# AK4493-Combi9.net
KiCad netlist of a schematic drawn in EAGLE
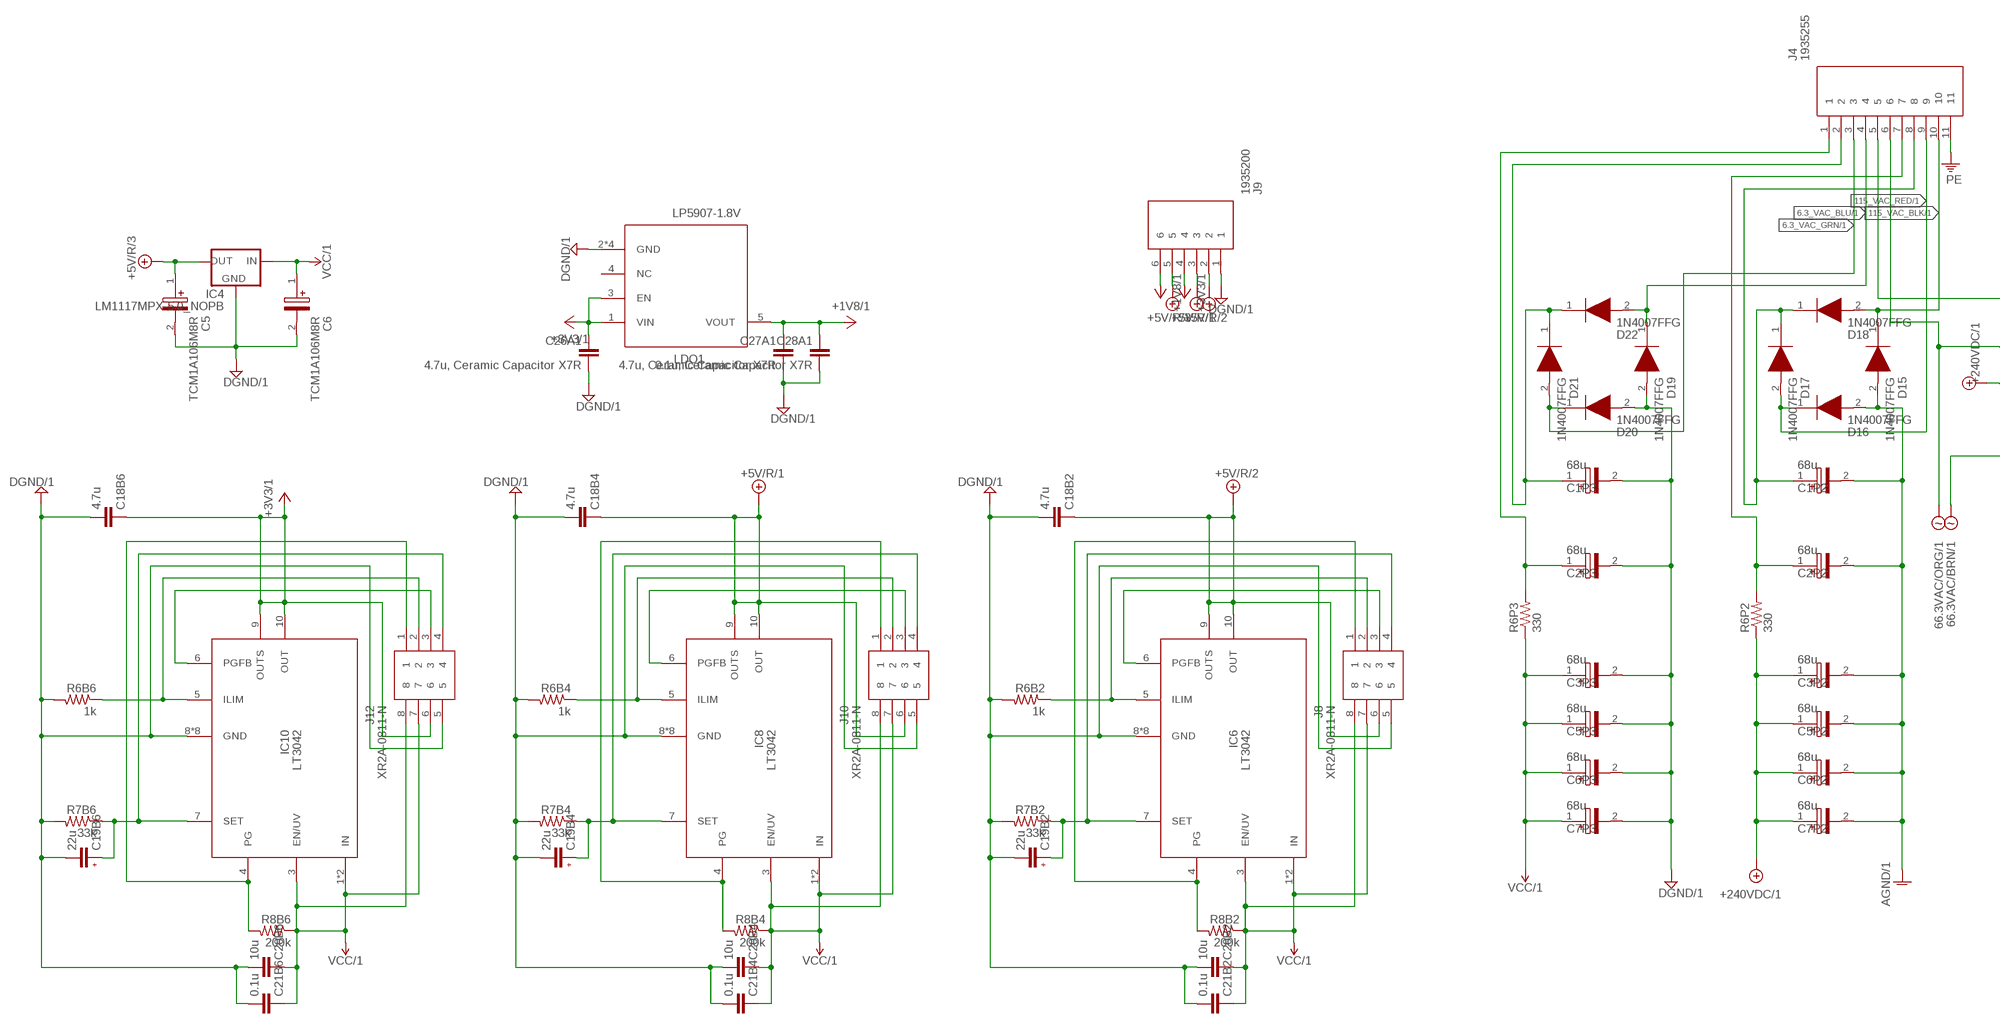
[diagram p0: schematic, sheet 1, part 1 of 3]
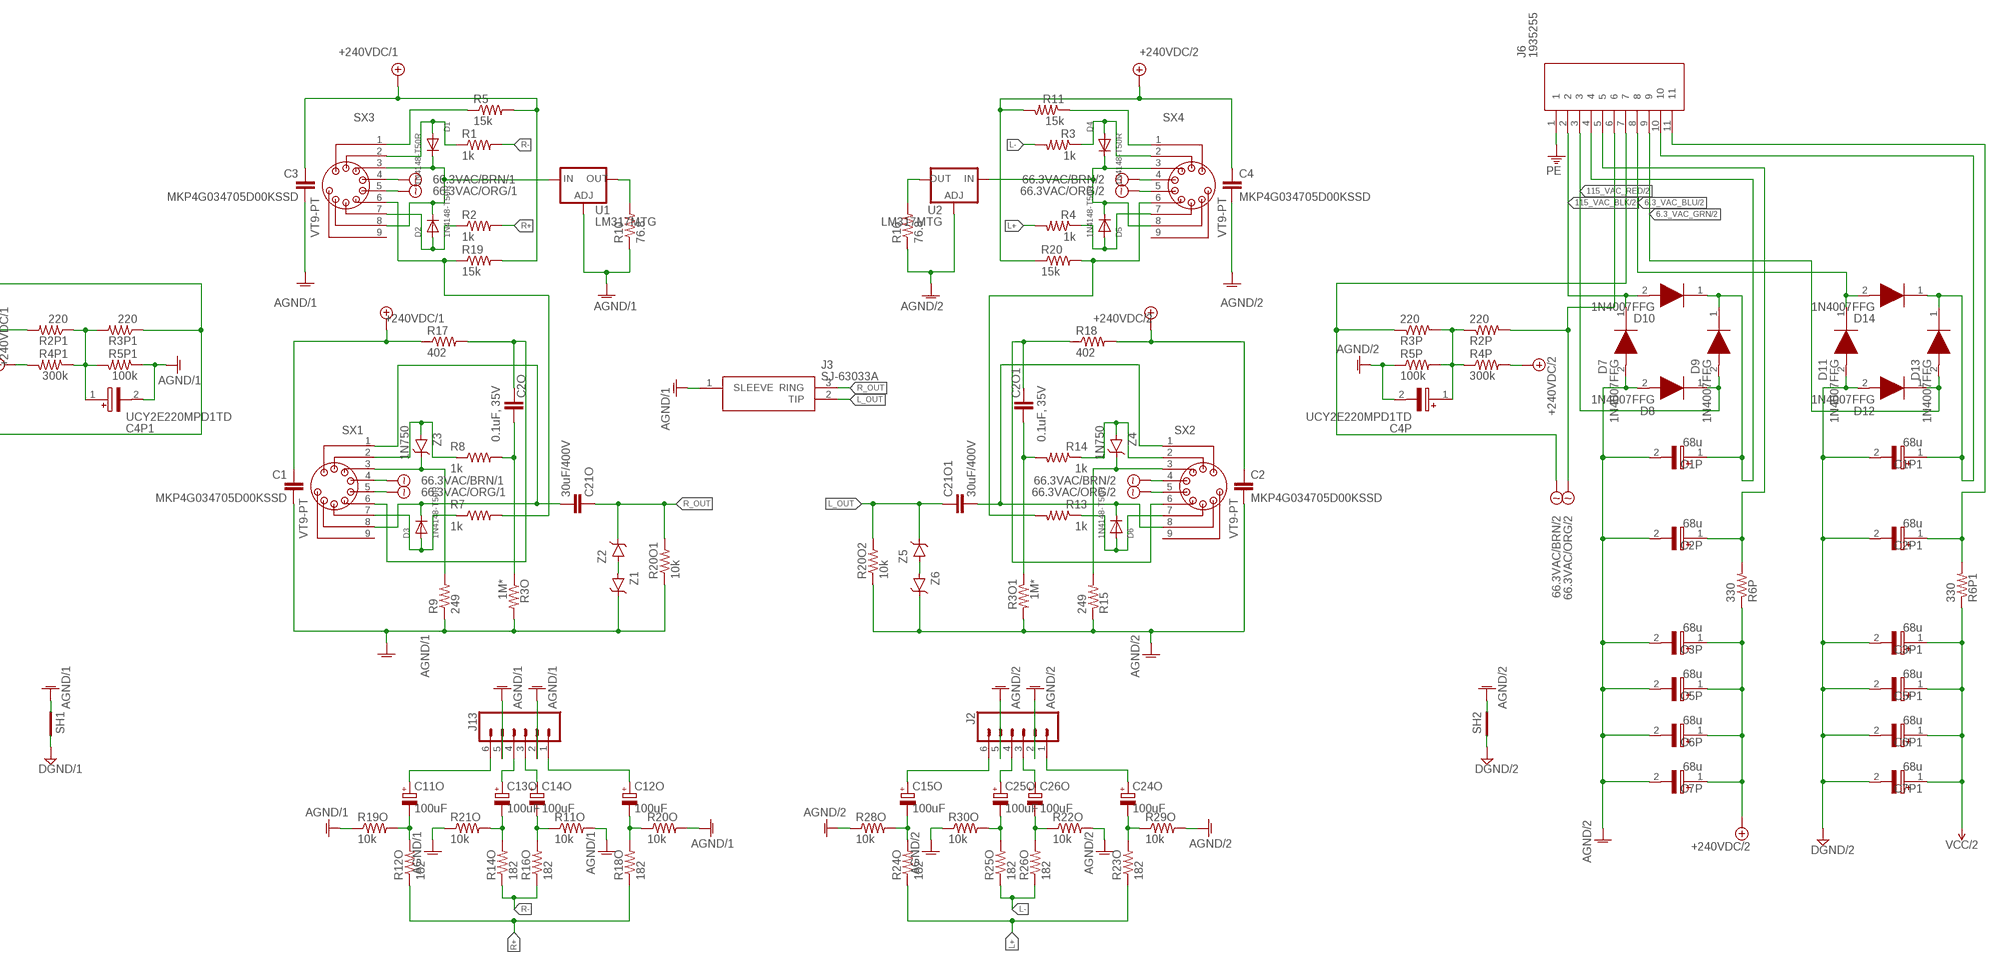
[diagram p1: schematic, sheet 1, part 2 of 3]
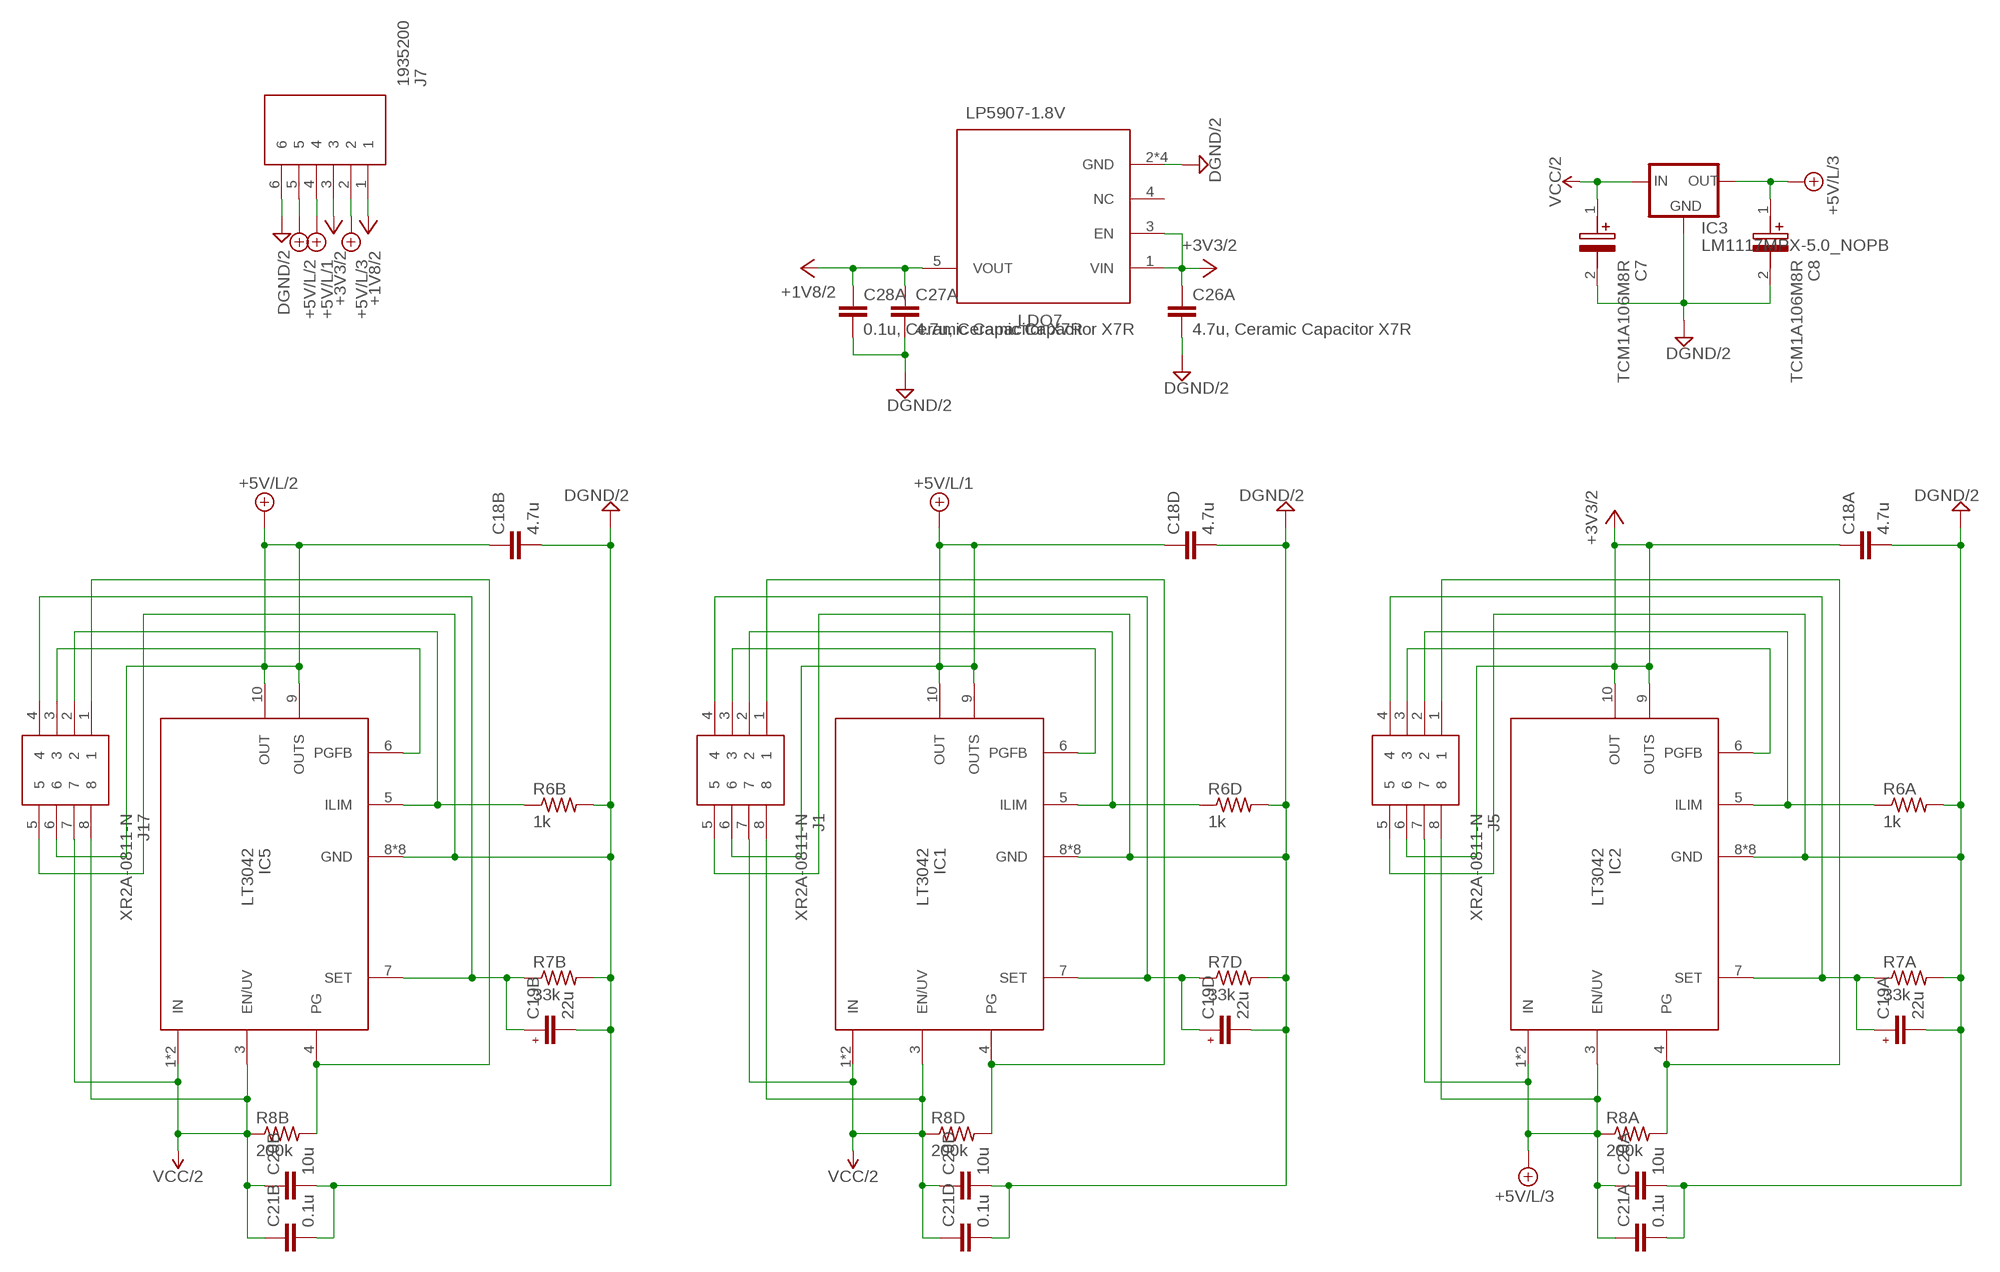
[diagram p2: schematic, sheet 1, part 3 of 3]

(export (version "E")
  (design (tool "Eeschema 10.0.6"))
  (components
    (comp (ref "C1")
      (value "MKP4G034705D00KSSD")
      (footprint "eagle-import:MKP4G034705D00KSSD")
      (fields (field (name "MOUSER_PART_NUMBER") "505-MKP4G034705DKSSD"))
      (libsource (lib "eagle-import") (part "MKP4G034705D00KSSD"))
    )
    (comp (ref "C1P")
      (value "68u")
      (footprint "eagle-import:CAPPRD750W80D1475H4700")
      (fields (field (name "MANUFACTURER_PART_NUMBER") "500HXW68MEFR14.5X45"))
      (libsource (lib "eagle-import") (part "500HXW68MEFR14.5X45"))
    )
    (comp (ref "C1P1")
      (value "68u")
      (footprint "eagle-import:CAPPRD750W80D1475H4700")
      (fields (field (name "MANUFACTURER_PART_NUMBER") "500HXW68MEFR14.5X45"))
      (libsource (lib "eagle-import") (part "500HXW68MEFR14.5X45"))
    )
    (comp (ref "C1P2")
      (value "68u")
      (footprint "eagle-import:CAPPRD750W80D1475H4700")
      (fields (field (name "MANUFACTURER_PART_NUMBER") "500HXW68MEFR14.5X45"))
      (libsource (lib "eagle-import") (part "500HXW68MEFR14.5X45"))
    )
    (comp (ref "C1P3")
      (value "68u")
      (footprint "eagle-import:CAPPRD750W80D1475H4700")
      (fields (field (name "MANUFACTURER_PART_NUMBER") "500HXW68MEFR14.5X45"))
      (libsource (lib "eagle-import") (part "500HXW68MEFR14.5X45"))
    )
    (comp (ref "C2")
      (value "MKP4G034705D00KSSD")
      (footprint "eagle-import:MKP4G034705D00KSSD")
      (fields (field (name "MOUSER_PART_NUMBER") "505-MKP4G034705DKSSD"))
      (libsource (lib "eagle-import") (part "MKP4G034705D00KSSD"))
    )
    (comp (ref "C2O")
      (value "0.1uF, 35V")
      (footprint "eagle-import:MKS4B031002A00JC00")
      (fields
        (field (name "MANUFACTURER_PART_NUMBER") "MKS4B031002A00JC00")
        (field (name "MOUSER_PART_NUMBER") "505-MKS4B0312AJC")
      )
      (libsource (lib "eagle-import") (part "MKS4B031002A00JC00"))
    )
    (comp (ref "C2O1")
      (value "0.1uF, 35V")
      (footprint "eagle-import:MKS4B031002A00JC00")
      (fields
        (field (name "MANUFACTURER_PART_NUMBER") "MKS4B031002A00JC00")
        (field (name "MOUSER_PART_NUMBER") "505-MKS4B0312AJC")
      )
      (libsource (lib "eagle-import") (part "MKS4B031002A00JC00"))
    )
    (comp (ref "C2P")
      (value "68u")
      (footprint "eagle-import:CAPPRD750W80D1475H4700")
      (fields (field (name "MANUFACTURER_PART_NUMBER") "500HXW68MEFR14.5X45"))
      (libsource (lib "eagle-import") (part "500HXW68MEFR14.5X45"))
    )
    (comp (ref "C2P1")
      (value "68u")
      (footprint "eagle-import:CAPPRD750W80D1475H4700")
      (fields (field (name "MANUFACTURER_PART_NUMBER") "500HXW68MEFR14.5X45"))
      (libsource (lib "eagle-import") (part "500HXW68MEFR14.5X45"))
    )
    (comp (ref "C2P2")
      (value "68u")
      (footprint "eagle-import:CAPPRD750W80D1475H4700")
      (fields (field (name "MANUFACTURER_PART_NUMBER") "500HXW68MEFR14.5X45"))
      (libsource (lib "eagle-import") (part "500HXW68MEFR14.5X45"))
    )
    (comp (ref "C2P3")
      (value "68u")
      (footprint "eagle-import:CAPPRD750W80D1475H4700")
      (fields (field (name "MANUFACTURER_PART_NUMBER") "500HXW68MEFR14.5X45"))
      (libsource (lib "eagle-import") (part "500HXW68MEFR14.5X45"))
    )
    (comp (ref "C3")
      (value "MKP4G034705D00KSSD")
      (footprint "eagle-import:MKP4G034705D00KSSD")
      (fields (field (name "MOUSER_PART_NUMBER") "505-MKP4G034705DKSSD"))
      (libsource (lib "eagle-import") (part "MKP4G034705D00KSSD"))
    )
    (comp (ref "C3P")
      (value "68u")
      (footprint "eagle-import:CAPPRD750W80D1475H4700")
      (fields (field (name "MANUFACTURER_PART_NUMBER") "500HXW68MEFR14.5X45"))
      (libsource (lib "eagle-import") (part "500HXW68MEFR14.5X45"))
    )
    (comp (ref "C3P1")
      (value "68u")
      (footprint "eagle-import:CAPPRD750W80D1475H4700")
      (fields (field (name "MANUFACTURER_PART_NUMBER") "500HXW68MEFR14.5X45"))
      (libsource (lib "eagle-import") (part "500HXW68MEFR14.5X45"))
    )
    (comp (ref "C3P2")
      (value "68u")
      (footprint "eagle-import:CAPPRD750W80D1475H4700")
      (fields (field (name "MANUFACTURER_PART_NUMBER") "500HXW68MEFR14.5X45"))
      (libsource (lib "eagle-import") (part "500HXW68MEFR14.5X45"))
    )
    (comp (ref "C3P3")
      (value "68u")
      (footprint "eagle-import:CAPPRD750W80D1475H4700")
      (fields (field (name "MANUFACTURER_PART_NUMBER") "500HXW68MEFR14.5X45"))
      (libsource (lib "eagle-import") (part "500HXW68MEFR14.5X45"))
    )
    (comp (ref "C4")
      (value "MKP4G034705D00KSSD")
      (footprint "eagle-import:MKP4G034705D00KSSD")
      (fields (field (name "MOUSER_PART_NUMBER") "505-MKP4G034705DKSSD"))
      (libsource (lib "eagle-import") (part "MKP4G034705D00KSSD"))
    )
    (comp (ref "C4P")
      (value "UCY2E220MPD1TD")
      (footprint "eagle-import:CAPPRD500W60D1025H1750")
      (fields (field (name "MOUSER_PART_NUMBER") "647-UCY2E220MPD1TD"))
      (libsource (lib "eagle-import") (part "UCY2E220MPD1TD"))
    )
    (comp (ref "C4P1")
      (value "UCY2E220MPD1TD")
      (footprint "eagle-import:CAPPRD500W60D1025H1750")
      (fields (field (name "MOUSER_PART_NUMBER") "647-UCY2E220MPD1TD"))
      (libsource (lib "eagle-import") (part "UCY2E220MPD1TD"))
    )
    (comp (ref "C5")
      (value "TCM1A106M8R")
      (footprint "eagle-import:CAPPM168X90N")
      (fields (field (name "MOUSER_PART_NUMBER") "755-TCM1A106M8R"))
      (libsource (lib "eagle-import") (part "TCM1A106M8R"))
    )
    (comp (ref "C5P")
      (value "68u")
      (footprint "eagle-import:CAPPRD750W80D1475H4700")
      (fields (field (name "MANUFACTURER_PART_NUMBER") "500HXW68MEFR14.5X45"))
      (libsource (lib "eagle-import") (part "500HXW68MEFR14.5X45"))
    )
    (comp (ref "C5P1")
      (value "68u")
      (footprint "eagle-import:CAPPRD750W80D1475H4700")
      (fields (field (name "MANUFACTURER_PART_NUMBER") "500HXW68MEFR14.5X45"))
      (libsource (lib "eagle-import") (part "500HXW68MEFR14.5X45"))
    )
    (comp (ref "C5P2")
      (value "68u")
      (footprint "eagle-import:CAPPRD750W80D1475H4700")
      (fields (field (name "MANUFACTURER_PART_NUMBER") "500HXW68MEFR14.5X45"))
      (libsource (lib "eagle-import") (part "500HXW68MEFR14.5X45"))
    )
    (comp (ref "C5P3")
      (value "68u")
      (footprint "eagle-import:CAPPRD750W80D1475H4700")
      (fields (field (name "MANUFACTURER_PART_NUMBER") "500HXW68MEFR14.5X45"))
      (libsource (lib "eagle-import") (part "500HXW68MEFR14.5X45"))
    )
    (comp (ref "C6")
      (value "TCM1A106M8R")
      (footprint "eagle-import:CAPPM168X90N")
      (fields (field (name "MOUSER_PART_NUMBER") "755-TCM1A106M8R"))
      (libsource (lib "eagle-import") (part "TCM1A106M8R"))
    )
    (comp (ref "C6P")
      (value "68u")
      (footprint "eagle-import:CAPPRD750W80D1475H4700")
      (fields (field (name "MANUFACTURER_PART_NUMBER") "500HXW68MEFR14.5X45"))
      (libsource (lib "eagle-import") (part "500HXW68MEFR14.5X45"))
    )
    (comp (ref "C6P1")
      (value "68u")
      (footprint "eagle-import:CAPPRD750W80D1475H4700")
      (fields (field (name "MANUFACTURER_PART_NUMBER") "500HXW68MEFR14.5X45"))
      (libsource (lib "eagle-import") (part "500HXW68MEFR14.5X45"))
    )
    (comp (ref "C6P2")
      (value "68u")
      (footprint "eagle-import:CAPPRD750W80D1475H4700")
      (fields (field (name "MANUFACTURER_PART_NUMBER") "500HXW68MEFR14.5X45"))
      (libsource (lib "eagle-import") (part "500HXW68MEFR14.5X45"))
    )
    (comp (ref "C6P3")
      (value "68u")
      (footprint "eagle-import:CAPPRD750W80D1475H4700")
      (fields (field (name "MANUFACTURER_PART_NUMBER") "500HXW68MEFR14.5X45"))
      (libsource (lib "eagle-import") (part "500HXW68MEFR14.5X45"))
    )
    (comp (ref "C7")
      (value "TCM1A106M8R")
      (footprint "eagle-import:CAPPM168X90N")
      (fields (field (name "MOUSER_PART_NUMBER") "755-TCM1A106M8R"))
      (libsource (lib "eagle-import") (part "TCM1A106M8R"))
    )
    (comp (ref "C7P")
      (value "68u")
      (footprint "eagle-import:CAPPRD750W80D1475H4700")
      (fields (field (name "MANUFACTURER_PART_NUMBER") "500HXW68MEFR14.5X45"))
      (libsource (lib "eagle-import") (part "500HXW68MEFR14.5X45"))
    )
    (comp (ref "C7P1")
      (value "68u")
      (footprint "eagle-import:CAPPRD750W80D1475H4700")
      (fields (field (name "MANUFACTURER_PART_NUMBER") "500HXW68MEFR14.5X45"))
      (libsource (lib "eagle-import") (part "500HXW68MEFR14.5X45"))
    )
    (comp (ref "C7P2")
      (value "68u")
      (footprint "eagle-import:CAPPRD750W80D1475H4700")
      (fields (field (name "MANUFACTURER_PART_NUMBER") "500HXW68MEFR14.5X45"))
      (libsource (lib "eagle-import") (part "500HXW68MEFR14.5X45"))
    )
    (comp (ref "C7P3")
      (value "68u")
      (footprint "eagle-import:CAPPRD750W80D1475H4700")
      (fields (field (name "MANUFACTURER_PART_NUMBER") "500HXW68MEFR14.5X45"))
      (libsource (lib "eagle-import") (part "500HXW68MEFR14.5X45"))
    )
    (comp (ref "C8")
      (value "TCM1A106M8R")
      (footprint "eagle-import:CAPPM168X90N")
      (fields (field (name "MOUSER_PART_NUMBER") "755-TCM1A106M8R"))
      (libsource (lib "eagle-import") (part "TCM1A106M8R"))
    )
    (comp (ref "C11O")
      (value "100uF")
      (footprint "eagle-import:CAPPRD350W60D825H1300")
      (fields
        (field (name "ARROW_PART_NUMBER") "UFW1H101MPD1TD")
        (field (name "MOUSER_PART_NUMBER") "647-UFW1H101MPD1TD")
      )
      (libsource (lib "eagle-import") (part "UFW1H101MPD1TD"))
    )
    (comp (ref "C12O")
      (value "100uF")
      (footprint "eagle-import:CAPPRD350W60D825H1300")
      (fields
        (field (name "ARROW_PART_NUMBER") "UFW1H101MPD1TD")
        (field (name "MOUSER_PART_NUMBER") "647-UFW1H101MPD1TD")
      )
      (libsource (lib "eagle-import") (part "UFW1H101MPD1TD"))
    )
    (comp (ref "C13O")
      (value "100uF")
      (footprint "eagle-import:CAPPRD350W60D825H1300")
      (fields
        (field (name "ARROW_PART_NUMBER") "UFW1H101MPD1TD")
        (field (name "MOUSER_PART_NUMBER") "647-UFW1H101MPD1TD")
      )
      (libsource (lib "eagle-import") (part "UFW1H101MPD1TD"))
    )
    (comp (ref "C14O")
      (value "100uF")
      (footprint "eagle-import:CAPPRD350W60D825H1300")
      (fields
        (field (name "ARROW_PART_NUMBER") "UFW1H101MPD1TD")
        (field (name "MOUSER_PART_NUMBER") "647-UFW1H101MPD1TD")
      )
      (libsource (lib "eagle-import") (part "UFW1H101MPD1TD"))
    )
    (comp (ref "C15O")
      (value "100uF")
      (footprint "eagle-import:CAPPRD350W60D825H1300")
      (fields
        (field (name "ARROW_PART_NUMBER") "UFW1H101MPD1TD")
        (field (name "MOUSER_PART_NUMBER") "647-UFW1H101MPD1TD")
      )
      (libsource (lib "eagle-import") (part "UFW1H101MPD1TD"))
    )
    (comp (ref "C18A")
      (value "4.7u")
      (footprint "eagle-import:CAPC2013X140N")
      (fields
        (field (name "MANUFACTURER_PART_NUMBER") "EMK212ABJ475KG-T")
        (field (name "MOUSER_PART_NUMBER") "963-EMK212ABJ475KG-T")
      )
      (libsource (lib "eagle-import") (part "EMK212ABJ475KG-T"))
    )
    (comp (ref "C18B")
      (value "4.7u")
      (footprint "eagle-import:CAPC2013X140N")
      (fields
        (field (name "MANUFACTURER_PART_NUMBER") "EMK212ABJ475KG-T")
        (field (name "MOUSER_PART_NUMBER") "963-EMK212ABJ475KG-T")
      )
      (libsource (lib "eagle-import") (part "EMK212ABJ475KG-T"))
    )
    (comp (ref "C18B2")
      (value "4.7u")
      (footprint "eagle-import:CAPC2013X140N")
      (fields
        (field (name "MANUFACTURER_PART_NUMBER") "EMK212ABJ475KG-T")
        (field (name "MOUSER_PART_NUMBER") "963-EMK212ABJ475KG-T")
      )
      (libsource (lib "eagle-import") (part "EMK212ABJ475KG-T"))
    )
    (comp (ref "C18B4")
      (value "4.7u")
      (footprint "eagle-import:CAPC2013X140N")
      (fields
        (field (name "MANUFACTURER_PART_NUMBER") "EMK212ABJ475KG-T")
        (field (name "MOUSER_PART_NUMBER") "963-EMK212ABJ475KG-T")
      )
      (libsource (lib "eagle-import") (part "EMK212ABJ475KG-T"))
    )
    (comp (ref "C18B6")
      (value "4.7u")
      (footprint "eagle-import:CAPC2013X140N")
      (fields
        (field (name "MANUFACTURER_PART_NUMBER") "EMK212ABJ475KG-T")
        (field (name "MOUSER_PART_NUMBER") "963-EMK212ABJ475KG-T")
      )
      (libsource (lib "eagle-import") (part "EMK212ABJ475KG-T"))
    )
    (comp (ref "C18D")
      (value "4.7u")
      (footprint "eagle-import:CAPC2013X140N")
      (fields
        (field (name "MANUFACTURER_PART_NUMBER") "EMK212ABJ475KG-T")
        (field (name "MOUSER_PART_NUMBER") "963-EMK212ABJ475KG-T")
      )
      (libsource (lib "eagle-import") (part "EMK212ABJ475KG-T"))
    )
    (comp (ref "C19A")
      (value "22u")
      (footprint "eagle-import:C1206")
      (fields
        (field (name "MANUFACTURER_PART_NUMBER") "EMK316BB7226ML-T")
        (field (name "MOUSER_PART_NUMBER") "963-EMK316BB7226ML-T")
      )
      (libsource (lib "eagle-import") (part "EMK316BB7226ML-T"))
    )
    (comp (ref "C19B")
      (value "22u")
      (footprint "eagle-import:C1206")
      (fields
        (field (name "MANUFACTURER_PART_NUMBER") "EMK316BB7226ML-T")
        (field (name "MOUSER_PART_NUMBER") "963-EMK316BB7226ML-T")
      )
      (libsource (lib "eagle-import") (part "EMK316BB7226ML-T"))
    )
    (comp (ref "C19B2")
      (value "22u")
      (footprint "eagle-import:C1206")
      (fields
        (field (name "MANUFACTURER_PART_NUMBER") "EMK316BB7226ML-T")
        (field (name "MOUSER_PART_NUMBER") "963-EMK316BB7226ML-T")
      )
      (libsource (lib "eagle-import") (part "EMK316BB7226ML-T"))
    )
    (comp (ref "C19B4")
      (value "22u")
      (footprint "eagle-import:C1206")
      (fields
        (field (name "MANUFACTURER_PART_NUMBER") "EMK316BB7226ML-T")
        (field (name "MOUSER_PART_NUMBER") "963-EMK316BB7226ML-T")
      )
      (libsource (lib "eagle-import") (part "EMK316BB7226ML-T"))
    )
    (comp (ref "C19B6")
      (value "22u")
      (footprint "eagle-import:C1206")
      (fields
        (field (name "MANUFACTURER_PART_NUMBER") "EMK316BB7226ML-T")
        (field (name "MOUSER_PART_NUMBER") "963-EMK316BB7226ML-T")
      )
      (libsource (lib "eagle-import") (part "EMK316BB7226ML-T"))
    )
    (comp (ref "C19D")
      (value "22u")
      (footprint "eagle-import:C1206")
      (fields
        (field (name "MANUFACTURER_PART_NUMBER") "EMK316BB7226ML-T")
        (field (name "MOUSER_PART_NUMBER") "963-EMK316BB7226ML-T")
      )
      (libsource (lib "eagle-import") (part "EMK316BB7226ML-T"))
    )
    (comp (ref "C20A")
      (value "10u")
      (footprint "eagle-import:CAPC2012X135N")
      (fields
        (field (name "MANUFACTURER_PART_NUMBER") "EMK212BB7106KG-T")
        (field (name "MOUSER_PART_NUMBER") "963-EMK212BB7106KG-T")
      )
      (libsource (lib "eagle-import") (part "EMK212BB7106KG-T"))
    )
    (comp (ref "C20B")
      (value "10u")
      (footprint "eagle-import:CAPC2012X135N")
      (fields
        (field (name "MANUFACTURER_PART_NUMBER") "EMK212BB7106KG-T")
        (field (name "MOUSER_PART_NUMBER") "963-EMK212BB7106KG-T")
      )
      (libsource (lib "eagle-import") (part "EMK212BB7106KG-T"))
    )
    (comp (ref "C20B2")
      (value "10u")
      (footprint "eagle-import:CAPC2012X135N")
      (fields
        (field (name "MANUFACTURER_PART_NUMBER") "EMK212BB7106KG-T")
        (field (name "MOUSER_PART_NUMBER") "963-EMK212BB7106KG-T")
      )
      (libsource (lib "eagle-import") (part "EMK212BB7106KG-T"))
    )
    (comp (ref "C20B4")
      (value "10u")
      (footprint "eagle-import:CAPC2012X135N")
      (fields
        (field (name "MANUFACTURER_PART_NUMBER") "EMK212BB7106KG-T")
        (field (name "MOUSER_PART_NUMBER") "963-EMK212BB7106KG-T")
      )
      (libsource (lib "eagle-import") (part "EMK212BB7106KG-T"))
    )
    (comp (ref "C20B6")
      (value "10u")
      (footprint "eagle-import:CAPC2012X135N")
      (fields
        (field (name "MANUFACTURER_PART_NUMBER") "EMK212BB7106KG-T")
        (field (name "MOUSER_PART_NUMBER") "963-EMK212BB7106KG-T")
      )
      (libsource (lib "eagle-import") (part "EMK212BB7106KG-T"))
    )
    (comp (ref "C20D")
      (value "10u")
      (footprint "eagle-import:CAPC2012X135N")
      (fields
        (field (name "MANUFACTURER_PART_NUMBER") "EMK212BB7106KG-T")
        (field (name "MOUSER_PART_NUMBER") "963-EMK212BB7106KG-T")
      )
      (libsource (lib "eagle-import") (part "EMK212BB7106KG-T"))
    )
    (comp (ref "C21A")
      (value "0.1u")
      (footprint "eagle-import:CAPC2012X135N")
      (fields
        (field (name "MANUFACTURER_PART_NUMBER") "EMF212B7104KGHT")
        (field (name "MOUSER_PART_NUMBER") "963-EMF212B7104KGHT")
      )
      (libsource (lib "eagle-import") (part "EMF212B7104KGHT"))
    )
    (comp (ref "C21B")
      (value "0.1u")
      (footprint "eagle-import:CAPC2012X135N")
      (fields
        (field (name "MANUFACTURER_PART_NUMBER") "EMF212B7104KGHT")
        (field (name "MOUSER_PART_NUMBER") "963-EMF212B7104KGHT")
      )
      (libsource (lib "eagle-import") (part "EMF212B7104KGHT"))
    )
    (comp (ref "C21B2")
      (value "0.1u")
      (footprint "eagle-import:CAPC2012X135N")
      (fields
        (field (name "MANUFACTURER_PART_NUMBER") "EMF212B7104KGHT")
        (field (name "MOUSER_PART_NUMBER") "963-EMF212B7104KGHT")
      )
      (libsource (lib "eagle-import") (part "EMF212B7104KGHT"))
    )
    (comp (ref "C21B4")
      (value "0.1u")
      (footprint "eagle-import:CAPC2012X135N")
      (fields
        (field (name "MANUFACTURER_PART_NUMBER") "EMF212B7104KGHT")
        (field (name "MOUSER_PART_NUMBER") "963-EMF212B7104KGHT")
      )
      (libsource (lib "eagle-import") (part "EMF212B7104KGHT"))
    )
    (comp (ref "C21B6")
      (value "0.1u")
      (footprint "eagle-import:CAPC2012X135N")
      (fields
        (field (name "MANUFACTURER_PART_NUMBER") "EMF212B7104KGHT")
        (field (name "MOUSER_PART_NUMBER") "963-EMF212B7104KGHT")
      )
      (libsource (lib "eagle-import") (part "EMF212B7104KGHT"))
    )
    (comp (ref "C21D")
      (value "0.1u")
      (footprint "eagle-import:CAPC2012X135N")
      (fields
        (field (name "MANUFACTURER_PART_NUMBER") "EMF212B7104KGHT")
        (field (name "MOUSER_PART_NUMBER") "963-EMF212B7104KGHT")
      )
      (libsource (lib "eagle-import") (part "EMF212B7104KGHT"))
    )
    (comp (ref "C21O")
      (value "30uF/400V")
      (footprint "eagle-import:DCP4G056007GD4KSSD")
      (fields
        (field (name "MANUFACTURER_PART_NUMBER") "DCP4G056007GD4KSSD")
        (field (name "MOUSER_PART_NUMBER") "505-DCP4G056007GD4KS")
      )
      (libsource (lib "eagle-import") (part "DCP4G056007GD4KSSD"))
    )
    (comp (ref "C21O1")
      (value "30uF/400V")
      (footprint "eagle-import:DCP4G056007GD4KSSD")
      (fields
        (field (name "MANUFACTURER_PART_NUMBER") "DCP4G056007GD4KSSD")
        (field (name "MOUSER_PART_NUMBER") "505-DCP4G056007GD4KS")
      )
      (libsource (lib "eagle-import") (part "DCP4G056007GD4KSSD"))
    )
    (comp (ref "C24O")
      (value "100uF")
      (footprint "eagle-import:CAPPRD350W60D825H1300")
      (fields
        (field (name "ARROW_PART_NUMBER") "UFW1H101MPD1TD")
        (field (name "MOUSER_PART_NUMBER") "647-UFW1H101MPD1TD")
      )
      (libsource (lib "eagle-import") (part "UFW1H101MPD1TD"))
    )
    (comp (ref "C25O")
      (value "100uF")
      (footprint "eagle-import:CAPPRD350W60D825H1300")
      (fields
        (field (name "ARROW_PART_NUMBER") "UFW1H101MPD1TD")
        (field (name "MOUSER_PART_NUMBER") "647-UFW1H101MPD1TD")
      )
      (libsource (lib "eagle-import") (part "UFW1H101MPD1TD"))
    )
    (comp (ref "C26A")
      (value "4.7u, Ceramic Capacitor X7R")
      (footprint "eagle-import:CAPC2013X140N")
      (fields
        (field (name "MANUFACTURER_PART_NUMBER") "EMK212ABJ475KG-T")
        (field (name "MOUSER_PART_NUMBER") "963-EMK212ABJ475KG-T")
      )
      (libsource (lib "eagle-import") (part "EMK212ABJ475KG-T"))
    )
    (comp (ref "C26A1")
      (value "4.7u, Ceramic Capacitor X7R")
      (footprint "eagle-import:CAPC2013X140N")
      (fields
        (field (name "MANUFACTURER_PART_NUMBER") "EMK212ABJ475KG-T")
        (field (name "MOUSER_PART_NUMBER") "963-EMK212ABJ475KG-T")
      )
      (libsource (lib "eagle-import") (part "EMK212ABJ475KG-T"))
    )
    (comp (ref "C26O")
      (value "100uF")
      (footprint "eagle-import:CAPPRD350W60D825H1300")
      (fields
        (field (name "ARROW_PART_NUMBER") "UFW1H101MPD1TD")
        (field (name "MOUSER_PART_NUMBER") "647-UFW1H101MPD1TD")
      )
      (libsource (lib "eagle-import") (part "UFW1H101MPD1TD"))
    )
    (comp (ref "C27A")
      (value "4.7u, Ceramic Capacitor X7R")
      (footprint "eagle-import:CAPC2013X140N")
      (fields
        (field (name "MANUFACTURER_PART_NUMBER") "EMK212ABJ475KG-T")
        (field (name "MOUSER_PART_NUMBER") "963-EMK212ABJ475KG-T")
      )
      (libsource (lib "eagle-import") (part "EMK212ABJ475KG-T"))
    )
    (comp (ref "C27A1")
      (value "4.7u, Ceramic Capacitor X7R")
      (footprint "eagle-import:CAPC2013X140N")
      (fields
        (field (name "MANUFACTURER_PART_NUMBER") "EMK212ABJ475KG-T")
        (field (name "MOUSER_PART_NUMBER") "963-EMK212ABJ475KG-T")
      )
      (libsource (lib "eagle-import") (part "EMK212ABJ475KG-T"))
    )
    (comp (ref "C28A")
      (value "0.1u, Ceramic Capacitor X7R")
      (footprint "eagle-import:CAPC2012X135N")
      (fields
        (field (name "MANUFACTURER_PART_NUMBER") "EMF212B7104KGHT")
        (field (name "MOUSER_PART_NUMBER") "963-EMF212B7104KGHT")
      )
      (libsource (lib "eagle-import") (part "EMF212B7104KGHT"))
    )
    (comp (ref "C28A1")
      (value "0.1u, Ceramic Capacitor X7R")
      (footprint "eagle-import:CAPC2012X135N")
      (fields
        (field (name "MANUFACTURER_PART_NUMBER") "EMF212B7104KGHT")
        (field (name "MOUSER_PART_NUMBER") "963-EMF212B7104KGHT")
      )
      (libsource (lib "eagle-import") (part "EMF212B7104KGHT"))
    )
    (comp (ref "D1")
      (value "1N4148-T50R")
      (footprint "eagle-import:DIOAD1068W53L380D172")
      (fields (field (name "MOUSER_PART_NUMBER") "512-1N4148T50R"))
      (libsource (lib "eagle-import") (part "1N4148-T50R"))
    )
    (comp (ref "D2")
      (value "1N4148-T50R")
      (footprint "eagle-import:DIOAD1068W53L380D172")
      (fields (field (name "MOUSER_PART_NUMBER") "512-1N4148T50R"))
      (libsource (lib "eagle-import") (part "1N4148-T50R"))
    )
    (comp (ref "D3")
      (value "1N4148-T50R")
      (footprint "eagle-import:DIOAD1068W53L380D172")
      (fields (field (name "MOUSER_PART_NUMBER") "512-1N4148T50R"))
      (libsource (lib "eagle-import") (part "1N4148-T50R"))
    )
    (comp (ref "D4")
      (value "1N4148-T50R")
      (footprint "eagle-import:DIOAD1068W53L380D172")
      (fields (field (name "MOUSER_PART_NUMBER") "512-1N4148T50R"))
      (libsource (lib "eagle-import") (part "1N4148-T50R"))
    )
    (comp (ref "D5")
      (value "1N4148-T50R")
      (footprint "eagle-import:DIOAD1068W53L380D172")
      (fields (field (name "MOUSER_PART_NUMBER") "512-1N4148T50R"))
      (libsource (lib "eagle-import") (part "1N4148-T50R"))
    )
    (comp (ref "D6")
      (value "1N4148-T50R")
      (footprint "eagle-import:DIOAD1068W53L380D172")
      (fields (field (name "MOUSER_PART_NUMBER") "512-1N4148T50R"))
      (libsource (lib "eagle-import") (part "1N4148-T50R"))
    )
    (comp (ref "D7")
      (value "1N4007FFG")
      (footprint "eagle-import:DIOAD1405W86L465D235")
      (fields (field (name "MOUSER_PART_NUMBER") "863-1N4007FFG"))
      (libsource (lib "eagle-import") (part "1N4007FFG"))
    )
    (comp (ref "D8")
      (value "1N4007FFG")
      (footprint "eagle-import:DIOAD1405W86L465D235")
      (fields (field (name "MOUSER_PART_NUMBER") "863-1N4007FFG"))
      (libsource (lib "eagle-import") (part "1N4007FFG"))
    )
    (comp (ref "D9")
      (value "1N4007FFG")
      (footprint "eagle-import:DIOAD1405W86L465D235")
      (fields (field (name "MOUSER_PART_NUMBER") "863-1N4007FFG"))
      (libsource (lib "eagle-import") (part "1N4007FFG"))
    )
    (comp (ref "D10")
      (value "1N4007FFG")
      (footprint "eagle-import:DIOAD1405W86L465D235")
      (fields (field (name "MOUSER_PART_NUMBER") "863-1N4007FFG"))
      (libsource (lib "eagle-import") (part "1N4007FFG"))
    )
    (comp (ref "D11")
      (value "1N4007FFG")
      (footprint "eagle-import:DIOAD1405W86L465D235")
      (fields (field (name "MOUSER_PART_NUMBER") "863-1N4007FFG"))
      (libsource (lib "eagle-import") (part "1N4007FFG"))
    )
    (comp (ref "D12")
      (value "1N4007FFG")
      (footprint "eagle-import:DIOAD1405W86L465D235")
      (fields (field (name "MOUSER_PART_NUMBER") "863-1N4007FFG"))
      (libsource (lib "eagle-import") (part "1N4007FFG"))
    )
    (comp (ref "D13")
      (value "1N4007FFG")
      (footprint "eagle-import:DIOAD1405W86L465D235")
      (fields (field (name "MOUSER_PART_NUMBER") "863-1N4007FFG"))
      (libsource (lib "eagle-import") (part "1N4007FFG"))
    )
    (comp (ref "D14")
      (value "1N4007FFG")
      (footprint "eagle-import:DIOAD1405W86L465D235")
      (fields (field (name "MOUSER_PART_NUMBER") "863-1N4007FFG"))
      (libsource (lib "eagle-import") (part "1N4007FFG"))
    )
    (comp (ref "D15")
      (value "1N4007FFG")
      (footprint "eagle-import:DIOAD1405W86L465D235")
      (fields (field (name "MOUSER_PART_NUMBER") "863-1N4007FFG"))
      (libsource (lib "eagle-import") (part "1N4007FFG"))
    )
    (comp (ref "D16")
      (value "1N4007FFG")
      (footprint "eagle-import:DIOAD1405W86L465D235")
      (fields (field (name "MOUSER_PART_NUMBER") "863-1N4007FFG"))
      (libsource (lib "eagle-import") (part "1N4007FFG"))
    )
    (comp (ref "D17")
      (value "1N4007FFG")
      (footprint "eagle-import:DIOAD1405W86L465D235")
      (fields (field (name "MOUSER_PART_NUMBER") "863-1N4007FFG"))
      (libsource (lib "eagle-import") (part "1N4007FFG"))
    )
    (comp (ref "D18")
      (value "1N4007FFG")
      (footprint "eagle-import:DIOAD1405W86L465D235")
      (fields (field (name "MOUSER_PART_NUMBER") "863-1N4007FFG"))
      (libsource (lib "eagle-import") (part "1N4007FFG"))
    )
    (comp (ref "D19")
      (value "1N4007FFG")
      (footprint "eagle-import:DIOAD1405W86L465D235")
      (fields (field (name "MOUSER_PART_NUMBER") "863-1N4007FFG"))
      (libsource (lib "eagle-import") (part "1N4007FFG"))
    )
    (comp (ref "D20")
      (value "1N4007FFG")
      (footprint "eagle-import:DIOAD1405W86L465D235")
      (fields (field (name "MOUSER_PART_NUMBER") "863-1N4007FFG"))
      (libsource (lib "eagle-import") (part "1N4007FFG"))
    )
    (comp (ref "D21")
      (value "1N4007FFG")
      (footprint "eagle-import:DIOAD1405W86L465D235")
      (fields (field (name "MOUSER_PART_NUMBER") "863-1N4007FFG"))
      (libsource (lib "eagle-import") (part "1N4007FFG"))
    )
    (comp (ref "D22")
      (value "1N4007FFG")
      (footprint "eagle-import:DIOAD1405W86L465D235")
      (fields (field (name "MOUSER_PART_NUMBER") "863-1N4007FFG"))
      (libsource (lib "eagle-import") (part "1N4007FFG"))
    )
    (comp (ref "IC1")
      (value "LT3042")
      (footprint "eagle-import:SOP50P490X110-11N")
      (fields
        (field (name "MANUFACTURER_PART_NUMBER") "LT3042EMSE#PBF")
        (field (name "MOUSER_PART_NUMBER") "584-LT3042EMSE#PBF")
      )
      (libsource (lib "eagle-import") (part "LT3042"))
    )
    (comp (ref "IC2")
      (value "LT3042")
      (footprint "eagle-import:SOP50P490X110-11N")
      (fields
        (field (name "MANUFACTURER_PART_NUMBER") "LT3042EMSE#PBF")
        (field (name "MOUSER_PART_NUMBER") "584-LT3042EMSE#PBF")
      )
      (libsource (lib "eagle-import") (part "LT3042"))
    )
    (comp (ref "IC3")
      (value "LM1117MPX-5.0_NOPB")
      (footprint "eagle-import:SOT230P700X180-4N")
      (fields
        (field (name "MANUFACTURER_PART_NUMBER") "LM1117MPX-5.0/NOPB")
        (field (name "MOUSER_PART_NUMBER") "926-LM1117MPX5.0NOPB")
      )
      (libsource (lib "eagle-import") (part "LM1117MPX-5.0_NOPB"))
    )
    (comp (ref "IC4")
      (value "LM1117MPX-5.0_NOPB")
      (footprint "eagle-import:SOT230P700X180-4N")
      (fields
        (field (name "MANUFACTURER_PART_NUMBER") "LM1117MPX-5.0/NOPB")
        (field (name "MOUSER_PART_NUMBER") "926-LM1117MPX5.0NOPB")
      )
      (libsource (lib "eagle-import") (part "LM1117MPX-5.0_NOPB"))
    )
    (comp (ref "IC5")
      (value "LT3042")
      (footprint "eagle-import:SOP50P490X110-11N")
      (fields
        (field (name "MANUFACTURER_PART_NUMBER") "LT3042EMSE#PBF")
        (field (name "MOUSER_PART_NUMBER") "584-LT3042EMSE#PBF")
      )
      (libsource (lib "eagle-import") (part "LT3042"))
    )
    (comp (ref "IC6")
      (value "LT3042")
      (footprint "eagle-import:SOP50P490X110-11N")
      (fields
        (field (name "MANUFACTURER_PART_NUMBER") "LT3042EMSE#PBF")
        (field (name "MOUSER_PART_NUMBER") "584-LT3042EMSE#PBF")
      )
      (libsource (lib "eagle-import") (part "LT3042"))
    )
    (comp (ref "IC8")
      (value "LT3042")
      (footprint "eagle-import:SOP50P490X110-11N")
      (fields
        (field (name "MANUFACTURER_PART_NUMBER") "LT3042EMSE#PBF")
        (field (name "MOUSER_PART_NUMBER") "584-LT3042EMSE#PBF")
      )
      (libsource (lib "eagle-import") (part "LT3042"))
    )
    (comp (ref "IC10")
      (value "LT3042")
      (footprint "eagle-import:SOP50P490X110-11N")
      (fields
        (field (name "MANUFACTURER_PART_NUMBER") "LT3042EMSE#PBF")
        (field (name "MOUSER_PART_NUMBER") "584-LT3042EMSE#PBF")
      )
      (libsource (lib "eagle-import") (part "LT3042"))
    )
    (comp (ref "J1")
      (value "XR2A-0811-N")
      (footprint "eagle-import:DIPS762W51P254L1016H390Q8N")
      (fields (field (name "MOUSER_PART_NUMBER") "653-XR2A-0811-N"))
      (libsource (lib "eagle-import") (part "XR2A-0811-N"))
    )
    (comp (ref "J2")
      (value "CONN_06SILK_FEMALE_PTH")
      (footprint "eagle-import:1X06")
      (libsource (lib "eagle-import") (part "CONN_06SILK_FEMALE_PTH"))
    )
    (comp (ref "J3")
      (value "SJ-63033A")
      (footprint "eagle-import:SJ63033A")
      (libsource (lib "eagle-import") (part "SJ-63033A"))
    )
    (comp (ref "J4")
      (value "1935255")
      (footprint "eagle-import:1935255")
      (fields (field (name "MOUSER_PART_NUMBER") "651-1935255"))
      (libsource (lib "eagle-import") (part "1935255"))
    )
    (comp (ref "J5")
      (value "XR2A-0811-N")
      (footprint "eagle-import:DIPS762W51P254L1016H390Q8N")
      (fields (field (name "MOUSER_PART_NUMBER") "653-XR2A-0811-N"))
      (libsource (lib "eagle-import") (part "XR2A-0811-N"))
    )
    (comp (ref "J6")
      (value "1935255")
      (footprint "eagle-import:1935255")
      (fields (field (name "MOUSER_PART_NUMBER") "651-1935255"))
      (libsource (lib "eagle-import") (part "Dual Mono Amp Library_47621477_1935255"))
    )
    (comp (ref "J7")
      (value "1935200")
      (footprint "eagle-import:1935200")
      (fields (field (name "MOUSER_PART_NUMBER") "651-1935200"))
      (libsource (lib "eagle-import") (part "Dual Mono Amp Library_47621477_1935200"))
    )
    (comp (ref "J8")
      (value "XR2A-0811-N")
      (footprint "eagle-import:DIPS762W51P254L1016H390Q8N")
      (fields (field (name "MOUSER_PART_NUMBER") "653-XR2A-0811-N"))
      (libsource (lib "eagle-import") (part "XR2A-0811-N"))
    )
    (comp (ref "J9")
      (value "1935200")
      (footprint "eagle-import:1935200")
      (fields (field (name "MOUSER_PART_NUMBER") "651-1935200"))
      (libsource (lib "eagle-import") (part "1935200"))
    )
    (comp (ref "J10")
      (value "XR2A-0811-N")
      (footprint "eagle-import:DIPS762W51P254L1016H390Q8N")
      (fields (field (name "MOUSER_PART_NUMBER") "653-XR2A-0811-N"))
      (libsource (lib "eagle-import") (part "XR2A-0811-N"))
    )
    (comp (ref "J12")
      (value "XR2A-0811-N")
      (footprint "eagle-import:DIPS762W51P254L1016H390Q8N")
      (fields (field (name "MOUSER_PART_NUMBER") "653-XR2A-0811-N"))
      (libsource (lib "eagle-import") (part "XR2A-0811-N"))
    )
    (comp (ref "J13")
      (value "CONN_06SILK_FEMALE_PTH")
      (footprint "eagle-import:1X06")
      (libsource (lib "eagle-import") (part "CONN_06SILK_FEMALE_PTH"))
    )
    (comp (ref "J17")
      (value "XR2A-0811-N")
      (footprint "eagle-import:DIPS762W51P254L1016H390Q8N")
      (fields (field (name "MOUSER_PART_NUMBER") "653-XR2A-0811-N"))
      (libsource (lib "eagle-import") (part "XR2A-0811-N"))
    )
    (comp (ref "LDO1")
      (value "LP5907-1.8V")
      (footprint "eagle-import:SOT95P280X145-5N")
      (fields
        (field (name "ARROW_PART_NUMBER") "LP5907MFX-1.8/NOPB")
        (field (name "MOUSER_PART_NUMBER") "595-LP5907MFX-1.8NPB")
      )
      (libsource (lib "eagle-import") (part "LP5907-1.8V"))
    )
    (comp (ref "LDO7")
      (value "LP5907-1.8V")
      (footprint "eagle-import:SOT95P280X145-5N")
      (fields
        (field (name "ARROW_PART_NUMBER") "LP5907MFX-1.8/NOPB")
        (field (name "MOUSER_PART_NUMBER") "595-LP5907MFX-1.8NPB")
      )
      (libsource (lib "eagle-import") (part "LP5907-1.8V"))
    )
    (comp (ref "R1")
      (value "1k")
      (footprint "eagle-import:0207_10")
      (fields
        (field (name "MANUFACTURER_PART_NUMBER") "LR1F1K0")
        (field (name "MOUSER_PART_NUMBER") "279-LR1F1K0")
      )
      (libsource (lib "eagle-import") (part "LR1F1K0"))
    )
    (comp (ref "R2")
      (value "1k")
      (footprint "eagle-import:0207_10")
      (fields
        (field (name "MANUFACTURER_PART_NUMBER") "LR1F1K0")
        (field (name "MOUSER_PART_NUMBER") "279-LR1F1K0")
      )
      (libsource (lib "eagle-import") (part "LR1F1K0"))
    )
    (comp (ref "R2P")
      (value "220")
      (footprint "eagle-import:0411_15")
      (libsource (lib "eagle-import") (part "R-US_0411/15"))
    )
    (comp (ref "R2P1")
      (value "220")
      (footprint "eagle-import:0411_15")
      (libsource (lib "eagle-import") (part "R-US_0411/15"))
    )
    (comp (ref "R3")
      (value "1k")
      (footprint "eagle-import:0207_10")
      (fields
        (field (name "MANUFACTURER_PART_NUMBER") "LR1F1K0")
        (field (name "MOUSER_PART_NUMBER") "279-LR1F1K0")
      )
      (libsource (lib "eagle-import") (part "LR1F1K0"))
    )
    (comp (ref "R3O")
      (value "1M*")
      (footprint "eagle-import:0207_10")
      (fields
        (field (name "MANUFACTURER_PART_NUMBER") "LR1F1M0")
        (field (name "MOUSER_PART_NUMBER") "279-LR1F1M0")
      )
      (libsource (lib "eagle-import") (part "LR1F1M0"))
    )
    (comp (ref "R3O1")
      (value "1M*")
      (footprint "eagle-import:0207_10")
      (fields
        (field (name "MANUFACTURER_PART_NUMBER") "LR1F1M0")
        (field (name "MOUSER_PART_NUMBER") "279-LR1F1M0")
      )
      (libsource (lib "eagle-import") (part "LR1F1M0"))
    )
    (comp (ref "R3P")
      (value "220")
      (footprint "eagle-import:0411_15")
      (libsource (lib "eagle-import") (part "R-US_0411/15"))
    )
    (comp (ref "R3P1")
      (value "220")
      (footprint "eagle-import:0411_15")
      (libsource (lib "eagle-import") (part "R-US_0411/15"))
    )
    (comp (ref "R4")
      (value "1k")
      (footprint "eagle-import:0207_10")
      (fields
        (field (name "MANUFACTURER_PART_NUMBER") "LR1F1K0")
        (field (name "MOUSER_PART_NUMBER") "279-LR1F1K0")
      )
      (libsource (lib "eagle-import") (part "LR1F1K0"))
    )
    (comp (ref "R4P")
      (value "300k")
      (footprint "eagle-import:0411_15")
      (libsource (lib "eagle-import") (part "R-US_0411/15"))
    )
    (comp (ref "R4P1")
      (value "300k")
      (footprint "eagle-import:0411_15")
      (libsource (lib "eagle-import") (part "R-US_0411/15"))
    )
    (comp (ref "R5")
      (value "15k")
      (footprint "eagle-import:0411_15")
      (fields
        (field (name "MANUFACTURER_PART_NUMBER") "CPF215K000FKE14")
        (field (name "MOUSER_PART_NUMBER") "71-CPF2-F-15K-E3")
      )
      (libsource (lib "eagle-import") (part "CPF215K000FKE14"))
    )
    (comp (ref "R5P")
      (value "100k")
      (footprint "eagle-import:0411_15")
      (libsource (lib "eagle-import") (part "R-US_0411/15"))
    )
    (comp (ref "R5P1")
      (value "100k")
      (footprint "eagle-import:0411_15")
      (libsource (lib "eagle-import") (part "R-US_0411/15"))
    )
    (comp (ref "R6A")
      (value "1k")
      (footprint "eagle-import:RESC2012X60N")
      (fields
        (field (name "MANUFACTURER_PART_NUMBER") "CHP0805-FX-1001ELF")
        (field (name "MOUSER_PART_NUMBER") "652-CHP0805FX1001ELF")
      )
      (libsource (lib "eagle-import") (part "CHP0805-FX-1001ELF"))
    )
    (comp (ref "R6B")
      (value "1k")
      (footprint "eagle-import:RESC2012X60N")
      (fields
        (field (name "MANUFACTURER_PART_NUMBER") "CHP0805-FX-1001ELF")
        (field (name "MOUSER_PART_NUMBER") "652-CHP0805FX1001ELF")
      )
      (libsource (lib "eagle-import") (part "CHP0805-FX-1001ELF"))
    )
    (comp (ref "R6B2")
      (value "1k")
      (footprint "eagle-import:RESC2012X60N")
      (fields
        (field (name "MANUFACTURER_PART_NUMBER") "CHP0805-FX-1001ELF")
        (field (name "MOUSER_PART_NUMBER") "652-CHP0805FX1001ELF")
      )
      (libsource (lib "eagle-import") (part "CHP0805-FX-1001ELF"))
    )
    (comp (ref "R6B4")
      (value "1k")
      (footprint "eagle-import:RESC2012X60N")
      (fields
        (field (name "MANUFACTURER_PART_NUMBER") "CHP0805-FX-1001ELF")
        (field (name "MOUSER_PART_NUMBER") "652-CHP0805FX1001ELF")
      )
      (libsource (lib "eagle-import") (part "CHP0805-FX-1001ELF"))
    )
    (comp (ref "R6B6")
      (value "1k")
      (footprint "eagle-import:RESC2012X60N")
      (fields
        (field (name "MANUFACTURER_PART_NUMBER") "CHP0805-FX-1001ELF")
        (field (name "MOUSER_PART_NUMBER") "652-CHP0805FX1001ELF")
      )
      (libsource (lib "eagle-import") (part "CHP0805-FX-1001ELF"))
    )
    (comp (ref "R6D")
      (value "1k")
      (footprint "eagle-import:RESC2012X60N")
      (fields
        (field (name "MANUFACTURER_PART_NUMBER") "CHP0805-FX-1001ELF")
        (field (name "MOUSER_PART_NUMBER") "652-CHP0805FX1001ELF")
      )
      (libsource (lib "eagle-import") (part "CHP0805-FX-1001ELF"))
    )
    (comp (ref "R6P")
      (value "330")
      (footprint "eagle-import:0411_15")
      (libsource (lib "eagle-import") (part "R-US_0411/15"))
    )
    (comp (ref "R6P1")
      (value "330")
      (footprint "eagle-import:0411_15")
      (libsource (lib "eagle-import") (part "R-US_0411/15"))
    )
    (comp (ref "R6P2")
      (value "330")
      (footprint "eagle-import:0411_15")
      (libsource (lib "eagle-import") (part "R-US_0411/15"))
    )
    (comp (ref "R6P3")
      (value "330")
      (footprint "eagle-import:0411_15")
      (libsource (lib "eagle-import") (part "R-US_0411/15"))
    )
    (comp (ref "R7")
      (value "1k")
      (footprint "eagle-import:0207_10")
      (fields
        (field (name "MANUFACTURER_PART_NUMBER") "LR1F1K0")
        (field (name "MOUSER_PART_NUMBER") "279-LR1F1K0")
      )
      (libsource (lib "eagle-import") (part "LR1F1K0"))
    )
    (comp (ref "R7A")
      (value "33k")
      (footprint "eagle-import:R0805")
      (fields
        (field (name "MANUFACTURER_PART_NUMBER") "CPF0805B51KE1")
        (field (name "MOUSER_PART_NUMBER") "279-CPF0805B51KE1")
      )
      (libsource (lib "eagle-import") (part "CPF0805B51KE1"))
    )
    (comp (ref "R7B")
      (value "33k")
      (footprint "eagle-import:R0805")
      (fields
        (field (name "MANUFACTURER_PART_NUMBER") "CPF0805B51KE1")
        (field (name "MOUSER_PART_NUMBER") "279-CPF0805B51KE1")
      )
      (libsource (lib "eagle-import") (part "CPF0805B51KE1"))
    )
    (comp (ref "R7B2")
      (value "33k")
      (footprint "eagle-import:R0805")
      (fields
        (field (name "MANUFACTURER_PART_NUMBER") "CPF0805B51KE1")
        (field (name "MOUSER_PART_NUMBER") "279-CPF0805B51KE1")
      )
      (libsource (lib "eagle-import") (part "CPF0805B51KE1"))
    )
    (comp (ref "R7B4")
      (value "33k")
      (footprint "eagle-import:R0805")
      (fields
        (field (name "MANUFACTURER_PART_NUMBER") "CPF0805B51KE1")
        (field (name "MOUSER_PART_NUMBER") "279-CPF0805B51KE1")
      )
      (libsource (lib "eagle-import") (part "CPF0805B51KE1"))
    )
    (comp (ref "R7B6")
      (value "33k")
      (footprint "eagle-import:R0805")
      (fields
        (field (name "MANUFACTURER_PART_NUMBER") "CPF0805B51KE1")
        (field (name "MOUSER_PART_NUMBER") "279-CPF0805B51KE1")
      )
      (libsource (lib "eagle-import") (part "CPF0805B51KE1"))
    )
    (comp (ref "R7D")
      (value "33k")
      (footprint "eagle-import:R0805")
      (fields
        (field (name "MANUFACTURER_PART_NUMBER") "CPF0805B51KE1")
        (field (name "MOUSER_PART_NUMBER") "279-CPF0805B51KE1")
      )
      (libsource (lib "eagle-import") (part "CPF0805B51KE1"))
    )
    (comp (ref "R8")
      (value "1k")
      (footprint "eagle-import:0207_10")
      (fields
        (field (name "MANUFACTURER_PART_NUMBER") "LR1F1K0")
        (field (name "MOUSER_PART_NUMBER") "279-LR1F1K0")
      )
      (libsource (lib "eagle-import") (part "LR1F1K0"))
    )
    (comp (ref "R8A")
      (value "200k")
      (footprint "eagle-import:R0805")
      (fields
        (field (name "MANUFACTURER_PART_NUMBER") "RR1220P-204-D")
        (field (name "MOUSER_PART_NUMBER") "754-RR1220P-204D")
      )
      (libsource (lib "eagle-import") (part "RR1220P-204-D"))
    )
    (comp (ref "R8B")
      (value "200k")
      (footprint "eagle-import:R0805")
      (fields
        (field (name "MANUFACTURER_PART_NUMBER") "RR1220P-204-D")
        (field (name "MOUSER_PART_NUMBER") "754-RR1220P-204D")
      )
      (libsource (lib "eagle-import") (part "RR1220P-204-D"))
    )
    (comp (ref "R8B2")
      (value "200k")
      (footprint "eagle-import:R0805")
      (fields
        (field (name "MANUFACTURER_PART_NUMBER") "RR1220P-204-D")
        (field (name "MOUSER_PART_NUMBER") "754-RR1220P-204D")
      )
      (libsource (lib "eagle-import") (part "RR1220P-204-D"))
    )
    (comp (ref "R8B4")
      (value "200k")
      (footprint "eagle-import:R0805")
      (fields
        (field (name "MANUFACTURER_PART_NUMBER") "RR1220P-204-D")
        (field (name "MOUSER_PART_NUMBER") "754-RR1220P-204D")
      )
      (libsource (lib "eagle-import") (part "RR1220P-204-D"))
    )
    (comp (ref "R8B6")
      (value "200k")
      (footprint "eagle-import:R0805")
      (fields
        (field (name "MANUFACTURER_PART_NUMBER") "RR1220P-204-D")
        (field (name "MOUSER_PART_NUMBER") "754-RR1220P-204D")
      )
      (libsource (lib "eagle-import") (part "RR1220P-204-D"))
    )
    (comp (ref "R8D")
      (value "200k")
      (footprint "eagle-import:R0805")
      (fields
        (field (name "MANUFACTURER_PART_NUMBER") "RR1220P-204-D")
        (field (name "MOUSER_PART_NUMBER") "754-RR1220P-204D")
      )
      (libsource (lib "eagle-import") (part "RR1220P-204-D"))
    )
    (comp (ref "R9")
      (value "249")
      (footprint "eagle-import:0207_10")
      (fields (field (name "MANUFACTURER_PART_NUMBER") "MBB02070C2490FRP00"))
      (libsource (lib "eagle-import") (part "MBB02070C2490FRP00"))
    )
    (comp (ref "R10")
      (value "76.8")
      (footprint "eagle-import:0207_10")
      (fields (field (name "MANUFACTURER_PART_NUMBER") "YR1B76R8CC"))
      (libsource (lib "eagle-import") (part "YR1B76R8CC"))
    )
    (comp (ref "R11")
      (value "15k")
      (footprint "eagle-import:0411_15")
      (fields
        (field (name "MANUFACTURER_PART_NUMBER") "CPF215K000FKE14")
        (field (name "MOUSER_PART_NUMBER") "71-CPF2-F-15K-E3")
      )
      (libsource (lib "eagle-import") (part "CPF215K000FKE14"))
    )
    (comp (ref "R11O")
      (value "10k")
      (footprint "eagle-import:0207_10")
      (fields
        (field (name "MANUFACTURER_PART_NUMBER") "LR1F10K")
        (field (name "MOUSER_PART_NUMBER") "279-LR1F10K")
      )
      (libsource (lib "eagle-import") (part "LR1F10K"))
    )
    (comp (ref "R12O")
      (value "182")
      (footprint "eagle-import:0207_10")
      (fields
        (field (name "MANUFACTURER") "Yageo")
        (field (name "MANUFACTURER_PART_NUMBER") "MF0207FTE52-182R")
        (field (name "MOUSER_PART_NUMBER") "603-MF0207FTE52-182R")
      )
      (libsource (lib "eagle-import") (part "MF0207FTE52-182R"))
    )
    (comp (ref "R13")
      (value "1k")
      (footprint "eagle-import:0207_10")
      (fields
        (field (name "MANUFACTURER_PART_NUMBER") "LR1F1K0")
        (field (name "MOUSER_PART_NUMBER") "279-LR1F1K0")
      )
      (libsource (lib "eagle-import") (part "LR1F1K0"))
    )
    (comp (ref "R14")
      (value "1k")
      (footprint "eagle-import:0207_10")
      (fields
        (field (name "MANUFACTURER_PART_NUMBER") "LR1F1K0")
        (field (name "MOUSER_PART_NUMBER") "279-LR1F1K0")
      )
      (libsource (lib "eagle-import") (part "LR1F1K0"))
    )
    (comp (ref "R14O")
      (value "182")
      (footprint "eagle-import:0207_10")
      (fields
        (field (name "MANUFACTURER") "Yageo")
        (field (name "MANUFACTURER_PART_NUMBER") "MF0207FTE52-182R")
        (field (name "MOUSER_PART_NUMBER") "603-MF0207FTE52-182R")
      )
      (libsource (lib "eagle-import") (part "MF0207FTE52-182R"))
    )
    (comp (ref "R15")
      (value "249")
      (footprint "eagle-import:0207_10")
      (fields (field (name "MANUFACTURER_PART_NUMBER") "MBB02070C2490FRP00"))
      (libsource (lib "eagle-import") (part "MBB02070C2490FRP00"))
    )
    (comp (ref "R16")
      (value "76.8")
      (footprint "eagle-import:0207_10")
      (fields (field (name "MANUFACTURER_PART_NUMBER") "YR1B76R8CC"))
      (libsource (lib "eagle-import") (part "YR1B76R8CC"))
    )
    (comp (ref "R16O")
      (value "182")
      (footprint "eagle-import:0207_10")
      (fields
        (field (name "MANUFACTURER") "Yageo")
        (field (name "MANUFACTURER_PART_NUMBER") "MF0207FTE52-182R")
        (field (name "MOUSER_PART_NUMBER") "603-MF0207FTE52-182R")
      )
      (libsource (lib "eagle-import") (part "MF0207FTE52-182R"))
    )
    (comp (ref "R17")
      (value "402")
      (footprint "eagle-import:0617_22")
      (fields (field (name "MANUFACTURER_PART_NUMBER") "RWR80S4020FRB12"))
      (libsource (lib "eagle-import") (part "RWR80S4020FRB12"))
    )
    (comp (ref "R18")
      (value "402")
      (footprint "eagle-import:0617_22")
      (fields (field (name "MANUFACTURER_PART_NUMBER") "RWR80S4020FRB12"))
      (libsource (lib "eagle-import") (part "RWR80S4020FRB12"))
    )
    (comp (ref "R18O")
      (value "182")
      (footprint "eagle-import:0207_10")
      (fields
        (field (name "MANUFACTURER") "Yageo")
        (field (name "MANUFACTURER_PART_NUMBER") "MF0207FTE52-182R")
        (field (name "MOUSER_PART_NUMBER") "603-MF0207FTE52-182R")
      )
      (libsource (lib "eagle-import") (part "MF0207FTE52-182R"))
    )
    (comp (ref "R19")
      (value "15k")
      (footprint "eagle-import:0411_15")
      (fields
        (field (name "MANUFACTURER_PART_NUMBER") "CPF215K000FKE14")
        (field (name "MOUSER_PART_NUMBER") "71-CPF2-F-15K-E3")
      )
      (libsource (lib "eagle-import") (part "CPF215K000FKE14"))
    )
    (comp (ref "R19O")
      (value "10k")
      (footprint "eagle-import:0207_10")
      (fields
        (field (name "MANUFACTURER_PART_NUMBER") "LR1F10K")
        (field (name "MOUSER_PART_NUMBER") "279-LR1F10K")
      )
      (libsource (lib "eagle-import") (part "LR1F10K"))
    )
    (comp (ref "R20")
      (value "15k")
      (footprint "eagle-import:0411_15")
      (fields
        (field (name "MANUFACTURER_PART_NUMBER") "CPF215K000FKE14")
        (field (name "MOUSER_PART_NUMBER") "71-CPF2-F-15K-E3")
      )
      (libsource (lib "eagle-import") (part "CPF215K000FKE14"))
    )
    (comp (ref "R20O")
      (value "10k")
      (footprint "eagle-import:0207_10")
      (fields
        (field (name "MANUFACTURER_PART_NUMBER") "LR1F10K")
        (field (name "MOUSER_PART_NUMBER") "279-LR1F10K")
      )
      (libsource (lib "eagle-import") (part "LR1F10K"))
    )
    (comp (ref "R20O1")
      (value "10k")
      (footprint "eagle-import:0207_10")
      (fields
        (field (name "MANUFACTURER_PART_NUMBER") "LR1F10K")
        (field (name "MOUSER_PART_NUMBER") "279-LR1F10K")
      )
      (libsource (lib "eagle-import") (part "LR1F10K"))
    )
    (comp (ref "R20O2")
      (value "10k")
      (footprint "eagle-import:0207_10")
      (fields
        (field (name "MANUFACTURER_PART_NUMBER") "LR1F10K")
        (field (name "MOUSER_PART_NUMBER") "279-LR1F10K")
      )
      (libsource (lib "eagle-import") (part "LR1F10K"))
    )
    (comp (ref "R21O")
      (value "10k")
      (footprint "eagle-import:0207_10")
      (fields
        (field (name "MANUFACTURER_PART_NUMBER") "LR1F10K")
        (field (name "MOUSER_PART_NUMBER") "279-LR1F10K")
      )
      (libsource (lib "eagle-import") (part "LR1F10K"))
    )
    (comp (ref "R22O")
      (value "10k")
      (footprint "eagle-import:0207_10")
      (fields
        (field (name "MANUFACTURER_PART_NUMBER") "LR1F10K")
        (field (name "MOUSER_PART_NUMBER") "279-LR1F10K")
      )
      (libsource (lib "eagle-import") (part "LR1F10K"))
    )
    (comp (ref "R23O")
      (value "182")
      (footprint "eagle-import:0207_10")
      (fields
        (field (name "MANUFACTURER") "Yageo")
        (field (name "MANUFACTURER_PART_NUMBER") "MF0207FTE52-182R")
        (field (name "MOUSER_PART_NUMBER") "603-MF0207FTE52-182R")
      )
      (libsource (lib "eagle-import") (part "MF0207FTE52-182R"))
    )
    (comp (ref "R24O")
      (value "182")
      (footprint "eagle-import:0207_10")
      (fields
        (field (name "MANUFACTURER") "Yageo")
        (field (name "MANUFACTURER_PART_NUMBER") "MF0207FTE52-182R")
        (field (name "MOUSER_PART_NUMBER") "603-MF0207FTE52-182R")
      )
      (libsource (lib "eagle-import") (part "MF0207FTE52-182R"))
    )
    (comp (ref "R25O")
      (value "182")
      (footprint "eagle-import:0207_10")
      (fields
        (field (name "MANUFACTURER") "Yageo")
        (field (name "MANUFACTURER_PART_NUMBER") "MF0207FTE52-182R")
        (field (name "MOUSER_PART_NUMBER") "603-MF0207FTE52-182R")
      )
      (libsource (lib "eagle-import") (part "MF0207FTE52-182R"))
    )
    (comp (ref "R26O")
      (value "182")
      (footprint "eagle-import:0207_10")
      (fields
        (field (name "MANUFACTURER") "Yageo")
        (field (name "MANUFACTURER_PART_NUMBER") "MF0207FTE52-182R")
        (field (name "MOUSER_PART_NUMBER") "603-MF0207FTE52-182R")
      )
      (libsource (lib "eagle-import") (part "MF0207FTE52-182R"))
    )
    (comp (ref "R28O")
      (value "10k")
      (footprint "eagle-import:0207_10")
      (fields
        (field (name "MANUFACTURER_PART_NUMBER") "LR1F10K")
        (field (name "MOUSER_PART_NUMBER") "279-LR1F10K")
      )
      (libsource (lib "eagle-import") (part "LR1F10K"))
    )
    (comp (ref "R29O")
      (value "10k")
      (footprint "eagle-import:0207_10")
      (fields
        (field (name "MANUFACTURER_PART_NUMBER") "LR1F10K")
        (field (name "MOUSER_PART_NUMBER") "279-LR1F10K")
      )
      (libsource (lib "eagle-import") (part "LR1F10K"))
    )
    (comp (ref "R30O")
      (value "10k")
      (footprint "eagle-import:0207_10")
      (fields
        (field (name "MANUFACTURER_PART_NUMBER") "LR1F10K")
        (field (name "MOUSER_PART_NUMBER") "279-LR1F10K")
      )
      (libsource (lib "eagle-import") (part "LR1F10K"))
    )
    (comp (ref "SH1")
      (value "SHORTA5")
      (footprint "eagle-import:SHORT_ALL-50")
      (libsource (lib "eagle-import") (part "SHORTA5"))
    )
    (comp (ref "SH2")
      (value "SHORTA5")
      (footprint "eagle-import:SHORT_ALL-50")
      (libsource (lib "eagle-import") (part "SHORTA5"))
    )
    (comp (ref "SX1")
      (value "VT9-PT")
      (footprint "eagle-import:VT9-PT")
      (libsource (lib "eagle-import") (part "VT9-PT"))
    )
    (comp (ref "SX2")
      (value "VT9-PT")
      (footprint "eagle-import:VT9-PT")
      (libsource (lib "eagle-import") (part "VT9-PT"))
    )
    (comp (ref "SX3")
      (value "VT9-PT")
      (footprint "eagle-import:VT9-PT")
      (libsource (lib "eagle-import") (part "VT9-PT"))
    )
    (comp (ref "SX4")
      (value "VT9-PT")
      (footprint "eagle-import:VT9-PT")
      (libsource (lib "eagle-import") (part "VT9-PT"))
    )
    (comp (ref "U1")
      (value "LM317MTG")
      (footprint "eagle-import:TO254P482X997X2018-3P")
      (fields (field (name "MOUSER_PART_NUMBER") "863-LM317MTG"))
      (libsource (lib "eagle-import") (part "LM317MTG"))
    )
    (comp (ref "U2")
      (value "LM317MTG")
      (footprint "eagle-import:TO254P482X997X2018-3P")
      (fields (field (name "MOUSER_PART_NUMBER") "863-LM317MTG"))
      (libsource (lib "eagle-import") (part "LM317MTG"))
    )
    (comp (ref "Z1")
      (value "BZX79-C16,113")
      (footprint "eagle-import:DIOAD1165W56L425D185")
      (libsource (lib "eagle-import") (part "BZX79-C16,113"))
    )
    (comp (ref "Z2")
      (value "BZX79-C16,113")
      (footprint "eagle-import:DIOAD1165W56L425D185")
      (libsource (lib "eagle-import") (part "BZX79-C16,113"))
    )
    (comp (ref "Z3")
      (value "1N750")
      (footprint "eagle-import:DIOAD1256W56L444D203")
      (fields (field (name "MOUSER_PART_NUMBER") "494-1N750(DO-35)"))
      (libsource (lib "eagle-import") (part "1N750"))
    )
    (comp (ref "Z4")
      (value "1N750")
      (footprint "eagle-import:DIOAD1256W56L444D203")
      (fields (field (name "MOUSER_PART_NUMBER") "494-1N750(DO-35)"))
      (libsource (lib "eagle-import") (part "1N750"))
    )
    (comp (ref "Z5")
      (value "BZX79-C16,113")
      (footprint "eagle-import:DIOAD1165W56L425D185")
      (libsource (lib "eagle-import") (part "BZX79-C16,113"))
    )
    (comp (ref "Z6")
      (value "BZX79-C16,113")
      (footprint "eagle-import:DIOAD1165W56L425D185")
      (libsource (lib "eagle-import") (part "BZX79-C16,113"))
    )
  )
  (nets
    (net (code "1") (name "+1V8{slash}1") (class "Default")
      (node (ref "C27A1") (pin "1") (pinfunction "1_1") (pintype "passive"))
      (node (ref "C28A1") (pin "1") (pinfunction "1_1") (pintype "passive"))
      (node (ref "J9") (pin "6") (pinfunction "6_6") (pintype "bidirectional"))
      (node (ref "LDO1") (pin "5") (pinfunction "VOUT_5") (pintype "bidirectional"))
    )
    (net (code "2") (name "+1V8{slash}2") (class "Default")
      (node (ref "C27A") (pin "1") (pinfunction "1_1") (pintype "passive"))
      (node (ref "C28A") (pin "1") (pinfunction "1_1") (pintype "passive"))
      (node (ref "J7") (pin "1") (pinfunction "1_1") (pintype "bidirectional"))
      (node (ref "LDO7") (pin "5") (pinfunction "VOUT_5") (pintype "bidirectional"))
    )
    (net (code "3") (name "+3V3{slash}1") (class "Default")
      (node (ref "C18B6") (pin "1") (pinfunction "1_1") (pintype "passive"))
      (node (ref "C26A1") (pin "1") (pinfunction "1_1") (pintype "passive"))
      (node (ref "IC10") (pin "10") (pinfunction "OUT_10") (pintype "bidirectional"))
      (node (ref "IC10") (pin "9") (pinfunction "OUTS_9") (pintype "bidirectional"))
      (node (ref "J12") (pin "6") (pinfunction "6_6") (pintype "bidirectional"))
      (node (ref "J9") (pin "4") (pinfunction "4_4") (pintype "bidirectional"))
      (node (ref "LDO1") (pin "1") (pinfunction "VIN_1") (pintype "bidirectional"))
      (node (ref "LDO1") (pin "3") (pinfunction "EN_3") (pintype "bidirectional"))
    )
    (net (code "4") (name "+3V3{slash}2") (class "Default")
      (node (ref "C18A") (pin "1") (pinfunction "1_1") (pintype "passive"))
      (node (ref "C26A") (pin "1") (pinfunction "1_1") (pintype "passive"))
      (node (ref "IC2") (pin "10") (pinfunction "OUT_10") (pintype "bidirectional"))
      (node (ref "IC2") (pin "9") (pinfunction "OUTS_9") (pintype "bidirectional"))
      (node (ref "J5") (pin "6") (pinfunction "6_6") (pintype "bidirectional"))
      (node (ref "J7") (pin "3") (pinfunction "3_3") (pintype "bidirectional"))
      (node (ref "LDO7") (pin "1") (pinfunction "VIN_1") (pintype "bidirectional"))
      (node (ref "LDO7") (pin "3") (pinfunction "EN_3") (pintype "bidirectional"))
    )
    (net (code "5") (name "+5V{slash}L{slash}1") (class "Default")
      (node (ref "C18D") (pin "1") (pinfunction "1_1") (pintype "passive"))
      (node (ref "IC1") (pin "10") (pinfunction "OUT_10") (pintype "bidirectional"))
      (node (ref "IC1") (pin "9") (pinfunction "OUTS_9") (pintype "bidirectional"))
      (node (ref "J1") (pin "6") (pinfunction "6_6") (pintype "bidirectional"))
      (node (ref "J7") (pin "4") (pinfunction "4_4") (pintype "bidirectional"))
    )
    (net (code "6") (name "+5V{slash}L{slash}2") (class "Default")
      (node (ref "C18B") (pin "1") (pinfunction "1_1") (pintype "passive"))
      (node (ref "IC5") (pin "10") (pinfunction "OUT_10") (pintype "bidirectional"))
      (node (ref "IC5") (pin "9") (pinfunction "OUTS_9") (pintype "bidirectional"))
      (node (ref "J17") (pin "6") (pinfunction "6_6") (pintype "bidirectional"))
      (node (ref "J7") (pin "5") (pinfunction "5_5") (pintype "bidirectional"))
    )
    (net (code "7") (name "+5V{slash}L{slash}3") (class "Default")
      (node (ref "C20A") (pin "1") (pinfunction "1_1") (pintype "passive"))
      (node (ref "C21A") (pin "1") (pinfunction "1_1") (pintype "passive"))
      (node (ref "C8") (pin "1") (pinfunction "+_1") (pintype "bidirectional"))
      (node (ref "IC2") (pin "1") (pinfunction "IN_1") (pintype "bidirectional"))
      (node (ref "IC2") (pin "2") (pinfunction "IN_2") (pintype "bidirectional"))
      (node (ref "IC2") (pin "3") (pinfunction "EN/UV_3") (pintype "bidirectional"))
      (node (ref "IC3") (pin "2") (pinfunction "OUT_2") (pintype "passive"))
      (node (ref "IC3") (pin "4") (pinfunction "OUT_4") (pintype "passive"))
      (node (ref "J5") (pin "7") (pinfunction "7_7") (pintype "bidirectional"))
      (node (ref "J5") (pin "8") (pinfunction "8_8") (pintype "bidirectional"))
      (node (ref "J7") (pin "2") (pinfunction "2_2") (pintype "bidirectional"))
      (node (ref "R8A") (pin "1") (pinfunction "1_1") (pintype "passive"))
    )
    (net (code "8") (name "+5V{slash}R{slash}1") (class "Default")
      (node (ref "C18B4") (pin "1") (pinfunction "1_1") (pintype "passive"))
      (node (ref "IC8") (pin "10") (pinfunction "OUT_10") (pintype "bidirectional"))
      (node (ref "IC8") (pin "9") (pinfunction "OUTS_9") (pintype "bidirectional"))
      (node (ref "J10") (pin "6") (pinfunction "6_6") (pintype "bidirectional"))
      (node (ref "J9") (pin "3") (pinfunction "3_3") (pintype "bidirectional"))
    )
    (net (code "9") (name "+5V{slash}R{slash}2") (class "Default")
      (node (ref "C18B2") (pin "1") (pinfunction "1_1") (pintype "passive"))
      (node (ref "IC6") (pin "10") (pinfunction "OUT_10") (pintype "bidirectional"))
      (node (ref "IC6") (pin "9") (pinfunction "OUTS_9") (pintype "bidirectional"))
      (node (ref "J8") (pin "6") (pinfunction "6_6") (pintype "bidirectional"))
      (node (ref "J9") (pin "2") (pinfunction "2_2") (pintype "bidirectional"))
    )
    (net (code "10") (name "+5V{slash}R{slash}3") (class "Default")
      (node (ref "C5") (pin "1") (pinfunction "+_1") (pintype "bidirectional"))
      (node (ref "IC4") (pin "2") (pinfunction "OUT_2") (pintype "passive"))
      (node (ref "IC4") (pin "4") (pinfunction "OUT_4") (pintype "passive"))
      (node (ref "J9") (pin "5") (pinfunction "5_5") (pintype "bidirectional"))
    )
    (net (code "11") (name "+240VDC{slash}1") (class "Default")
      (node (ref "C1") (pin "1") (pinfunction "1_1") (pintype "passive"))
      (node (ref "C3") (pin "1") (pinfunction "1_1") (pintype "passive"))
      (node (ref "C3P2") (pin "1") (pinfunction "+_1") (pintype "bidirectional"))
      (node (ref "C5P2") (pin "1") (pinfunction "+_1") (pintype "bidirectional"))
      (node (ref "C6P2") (pin "1") (pinfunction "+_1") (pintype "bidirectional"))
      (node (ref "C7P2") (pin "1") (pinfunction "+_1") (pintype "bidirectional"))
      (node (ref "R17") (pin "1") (pinfunction "1_1") (pintype "passive"))
      (node (ref "R19") (pin "2") (pinfunction "2_2") (pintype "passive"))
      (node (ref "R4P1") (pin "2") (pinfunction "2_2") (pintype "passive"))
      (node (ref "R5") (pin "2") (pinfunction "2_2") (pintype "passive"))
      (node (ref "R6P2") (pin "1") (pinfunction "1_1") (pintype "passive"))
    )
    (net (code "12") (name "+240VDC{slash}2") (class "Default")
      (node (ref "C2") (pin "1") (pinfunction "1_1") (pintype "passive"))
      (node (ref "C3P") (pin "1") (pinfunction "+_1") (pintype "bidirectional"))
      (node (ref "C4") (pin "1") (pinfunction "1_1") (pintype "passive"))
      (node (ref "C5P") (pin "1") (pinfunction "+_1") (pintype "bidirectional"))
      (node (ref "C6P") (pin "1") (pinfunction "+_1") (pintype "bidirectional"))
      (node (ref "C7P") (pin "1") (pinfunction "+_1") (pintype "bidirectional"))
      (node (ref "R11") (pin "2") (pinfunction "2_2") (pintype "passive"))
      (node (ref "R18") (pin "2") (pinfunction "2_2") (pintype "passive"))
      (node (ref "R20") (pin "1") (pinfunction "1_1") (pintype "passive"))
      (node (ref "R4P") (pin "2") (pinfunction "2_2") (pintype "passive"))
      (node (ref "R6P") (pin "1") (pinfunction "1_1") (pintype "passive"))
    )
    (net (code "13") (name "6.3_VAC_BLU{slash}1") (class "Default")
      (node (ref "D19") (pin "1") (pinfunction "K_1") (pintype "bidirectional"))
      (node (ref "D22") (pin "2") (pinfunction "A_2") (pintype "bidirectional"))
      (node (ref "J4") (pin "4") (pinfunction "4_4") (pintype "bidirectional"))
    )
    (net (code "14") (name "6.3_VAC_BLU{slash}2") (class "Default")
      (node (ref "D11") (pin "1") (pinfunction "K_1") (pintype "bidirectional"))
      (node (ref "D14") (pin "2") (pinfunction "A_2") (pintype "bidirectional"))
      (node (ref "J6") (pin "8") (pinfunction "8_8") (pintype "bidirectional"))
    )
    (net (code "15") (name "6.3_VAC_GRN{slash}1") (class "Default")
      (node (ref "D20") (pin "1") (pinfunction "K_1") (pintype "bidirectional"))
      (node (ref "D21") (pin "2") (pinfunction "A_2") (pintype "bidirectional"))
      (node (ref "J4") (pin "3") (pinfunction "3_3") (pintype "bidirectional"))
    )
    (net (code "16") (name "6.3_VAC_GRN{slash}2") (class "Default")
      (node (ref "D12") (pin "1") (pinfunction "K_1") (pintype "bidirectional"))
      (node (ref "D13") (pin "2") (pinfunction "A_2") (pintype "bidirectional"))
      (node (ref "J6") (pin "9") (pinfunction "9_9") (pintype "bidirectional"))
    )
    (net (code "17") (name "66.3VAC{slash}BRN{slash}1") (class "Default")
      (node (ref "J4") (pin "5") (pinfunction "5_5") (pintype "bidirectional"))
      (node (ref "R3P1") (pin "1") (pinfunction "1_1") (pintype "passive"))
      (node (ref "SX1") (pin "4") (pinfunction "4_4") (pintype "passive"))
      (node (ref "SX3") (pin "4") (pinfunction "4_4") (pintype "passive"))
    )
    (net (code "18") (name "66.3VAC{slash}BRN{slash}2") (class "Default")
      (node (ref "J6") (pin "7") (pinfunction "7_7") (pintype "bidirectional"))
      (node (ref "R3P") (pin "1") (pinfunction "1_1") (pintype "passive"))
      (node (ref "SX2") (pin "4") (pinfunction "4_4") (pintype "passive"))
      (node (ref "SX4") (pin "4") (pinfunction "4_4") (pintype "passive"))
    )
    (net (code "19") (name "66.3VAC{slash}ORG{slash}1") (class "Default")
      (node (ref "J4") (pin "6") (pinfunction "6_6") (pintype "bidirectional"))
      (node (ref "R2P1") (pin "2") (pinfunction "2_2") (pintype "passive"))
      (node (ref "SX1") (pin "5") (pinfunction "5_5") (pintype "passive"))
      (node (ref "SX3") (pin "5") (pinfunction "5_5") (pintype "passive"))
    )
    (net (code "20") (name "66.3VAC{slash}ORG{slash}2") (class "Default")
      (node (ref "J6") (pin "6") (pinfunction "6_6") (pintype "bidirectional"))
      (node (ref "R2P") (pin "2") (pinfunction "2_2") (pintype "passive"))
      (node (ref "SX2") (pin "5") (pinfunction "5_5") (pintype "passive"))
      (node (ref "SX4") (pin "5") (pinfunction "5_5") (pintype "passive"))
    )
    (net (code "21") (name "115_VAC_BLK{slash}1") (class "Default")
      (node (ref "D15") (pin "1") (pinfunction "K_1") (pintype "bidirectional"))
      (node (ref "D18") (pin "2") (pinfunction "A_2") (pintype "bidirectional"))
      (node (ref "J4") (pin "10") (pinfunction "10_10") (pintype "bidirectional"))
    )
    (net (code "22") (name "115_VAC_BLK{slash}2") (class "Default")
      (node (ref "D10") (pin "2") (pinfunction "A_2") (pintype "bidirectional"))
      (node (ref "D7") (pin "1") (pinfunction "K_1") (pintype "bidirectional"))
      (node (ref "J6") (pin "2") (pinfunction "2_2") (pintype "bidirectional"))
    )
    (net (code "23") (name "115_VAC_RED{slash}1") (class "Default")
      (node (ref "D16") (pin "1") (pinfunction "K_1") (pintype "bidirectional"))
      (node (ref "D17") (pin "2") (pinfunction "A_2") (pintype "bidirectional"))
      (node (ref "J4") (pin "9") (pinfunction "9_9") (pintype "bidirectional"))
    )
    (net (code "24") (name "115_VAC_RED{slash}2") (class "Default")
      (node (ref "D8") (pin "1") (pinfunction "K_1") (pintype "bidirectional"))
      (node (ref "D9") (pin "2") (pinfunction "A_2") (pintype "bidirectional"))
      (node (ref "J6") (pin "3") (pinfunction "3_3") (pintype "bidirectional"))
    )
    (net (code "25") (name "AGND{slash}1") (class "Default")
      (node (ref "C1") (pin "2") (pinfunction "2_2") (pintype "passive"))
      (node (ref "C1P2") (pin "2") (pinfunction "-_2") (pintype "bidirectional"))
      (node (ref "C2P2") (pin "2") (pinfunction "-_2") (pintype "bidirectional"))
      (node (ref "C3") (pin "2") (pinfunction "2_2") (pintype "passive"))
      (node (ref "C3P2") (pin "2") (pinfunction "-_2") (pintype "bidirectional"))
      (node (ref "C4P1") (pin "2") (pinfunction "-_2") (pintype "bidirectional"))
      (node (ref "C5P2") (pin "2") (pinfunction "-_2") (pintype "bidirectional"))
      (node (ref "C6P2") (pin "2") (pinfunction "-_2") (pintype "bidirectional"))
      (node (ref "C7P2") (pin "2") (pinfunction "-_2") (pintype "bidirectional"))
      (node (ref "D15") (pin "2") (pinfunction "A_2") (pintype "bidirectional"))
      (node (ref "D16") (pin "2") (pinfunction "A_2") (pintype "bidirectional"))
      (node (ref "J13") (pin "2") (pinfunction "2_2") (pintype "passive"))
      (node (ref "J13") (pin "5") (pinfunction "5_5") (pintype "passive"))
      (node (ref "J3") (pin "1") (pinfunction "SLEEVE_1") (pintype "bidirectional"))
      (node (ref "R10") (pin "1") (pinfunction "1_1") (pintype "passive"))
      (node (ref "R11O") (pin "2") (pinfunction "2_2") (pintype "passive"))
      (node (ref "R19O") (pin "1") (pinfunction "1_1") (pintype "passive"))
      (node (ref "R20O") (pin "2") (pinfunction "2_2") (pintype "passive"))
      (node (ref "R20O1") (pin "1") (pinfunction "1_1") (pintype "passive"))
      (node (ref "R21O") (pin "1") (pinfunction "1_1") (pintype "passive"))
      (node (ref "R3O") (pin "2") (pinfunction "2_2") (pintype "passive"))
      (node (ref "R5P1") (pin "1") (pinfunction "1_1") (pintype "passive"))
      (node (ref "R9") (pin "1") (pinfunction "1_1") (pintype "passive"))
      (node (ref "SH1") (pin "2") (pinfunction "P$2_2") (pintype "bidirectional"))
      (node (ref "U1") (pin "1") (pinfunction "ADJ_1") (pintype "input"))
      (node (ref "Z1") (pin "1") (pinfunction "C_1") (pintype "passive"))
    )
    (net (code "26") (name "AGND{slash}2") (class "Default")
      (node (ref "C1P") (pin "2") (pinfunction "-_2") (pintype "bidirectional"))
      (node (ref "C2") (pin "2") (pinfunction "2_2") (pintype "passive"))
      (node (ref "C2P") (pin "2") (pinfunction "-_2") (pintype "bidirectional"))
      (node (ref "C3P") (pin "2") (pinfunction "-_2") (pintype "bidirectional"))
      (node (ref "C4") (pin "2") (pinfunction "2_2") (pintype "passive"))
      (node (ref "C4P") (pin "2") (pinfunction "-_2") (pintype "bidirectional"))
      (node (ref "C5P") (pin "2") (pinfunction "-_2") (pintype "bidirectional"))
      (node (ref "C6P") (pin "2") (pinfunction "-_2") (pintype "bidirectional"))
      (node (ref "C7P") (pin "2") (pinfunction "-_2") (pintype "bidirectional"))
      (node (ref "D7") (pin "2") (pinfunction "A_2") (pintype "bidirectional"))
      (node (ref "D8") (pin "2") (pinfunction "A_2") (pintype "bidirectional"))
      (node (ref "J2") (pin "2") (pinfunction "2_2") (pintype "passive"))
      (node (ref "J2") (pin "5") (pinfunction "5_5") (pintype "passive"))
      (node (ref "R15") (pin "1") (pinfunction "1_1") (pintype "passive"))
      (node (ref "R16") (pin "1") (pinfunction "1_1") (pintype "passive"))
      (node (ref "R20O2") (pin "1") (pinfunction "1_1") (pintype "passive"))
      (node (ref "R22O") (pin "2") (pinfunction "2_2") (pintype "passive"))
      (node (ref "R28O") (pin "1") (pinfunction "1_1") (pintype "passive"))
      (node (ref "R29O") (pin "2") (pinfunction "2_2") (pintype "passive"))
      (node (ref "R30O") (pin "1") (pinfunction "1_1") (pintype "passive"))
      (node (ref "R3O1") (pin "2") (pinfunction "2_2") (pintype "passive"))
      (node (ref "R5P") (pin "1") (pinfunction "1_1") (pintype "passive"))
      (node (ref "SH2") (pin "2") (pinfunction "P$2_2") (pintype "bidirectional"))
      (node (ref "U2") (pin "1") (pinfunction "ADJ_1") (pintype "input"))
      (node (ref "Z6") (pin "1") (pinfunction "C_1") (pintype "passive"))
    )
    (net (code "27") (name "DGND{slash}1") (class "Default")
      (node (ref "C18B2") (pin "2") (pinfunction "2_2") (pintype "passive"))
      (node (ref "C18B4") (pin "2") (pinfunction "2_2") (pintype "passive"))
      (node (ref "C18B6") (pin "2") (pinfunction "2_2") (pintype "passive"))
      (node (ref "C19B2") (pin "2") (pinfunction "2_2") (pintype "passive"))
      (node (ref "C19B2") (pin "DGND") (pinfunction "2_DGND") (pintype "passive"))
      (node (ref "C19B4") (pin "2") (pinfunction "2_2") (pintype "passive"))
      (node (ref "C19B4") (pin "DGND") (pinfunction "2_DGND") (pintype "passive"))
      (node (ref "C19B6") (pin "2") (pinfunction "2_2") (pintype "passive"))
      (node (ref "C19B6") (pin "DGND") (pinfunction "2_DGND") (pintype "passive"))
      (node (ref "C1P3") (pin "2") (pinfunction "-_2") (pintype "bidirectional"))
      (node (ref "C20B2") (pin "2") (pinfunction "2_2") (pintype "passive"))
      (node (ref "C20B4") (pin "2") (pinfunction "2_2") (pintype "passive"))
      (node (ref "C20B6") (pin "2") (pinfunction "2_2") (pintype "passive"))
      (node (ref "C21B2") (pin "2") (pinfunction "2_2") (pintype "passive"))
      (node (ref "C21B4") (pin "2") (pinfunction "2_2") (pintype "passive"))
      (node (ref "C21B6") (pin "2") (pinfunction "2_2") (pintype "passive"))
      (node (ref "C26A1") (pin "2") (pinfunction "2_2") (pintype "passive"))
      (node (ref "C27A1") (pin "2") (pinfunction "2_2") (pintype "passive"))
      (node (ref "C28A1") (pin "2") (pinfunction "2_2") (pintype "passive"))
      (node (ref "C2P3") (pin "2") (pinfunction "-_2") (pintype "bidirectional"))
      (node (ref "C3P3") (pin "2") (pinfunction "-_2") (pintype "bidirectional"))
      (node (ref "C5") (pin "2") (pinfunction "-_2") (pintype "bidirectional"))
      (node (ref "C5P3") (pin "2") (pinfunction "-_2") (pintype "bidirectional"))
      (node (ref "C6") (pin "2") (pinfunction "-_2") (pintype "bidirectional"))
      (node (ref "C6P3") (pin "2") (pinfunction "-_2") (pintype "bidirectional"))
      (node (ref "C7P3") (pin "2") (pinfunction "-_2") (pintype "bidirectional"))
      (node (ref "D19") (pin "2") (pinfunction "A_2") (pintype "bidirectional"))
      (node (ref "D20") (pin "2") (pinfunction "A_2") (pintype "bidirectional"))
      (node (ref "IC10") (pin "11") (pinfunction "GND_11") (pintype "bidirectional"))
      (node (ref "IC10") (pin "8") (pinfunction "GND_8") (pintype "bidirectional"))
      (node (ref "IC10") (pin "P$1") (pinfunction "GND_P$1") (pintype "bidirectional"))
      (node (ref "IC10") (pin "P$2") (pinfunction "GND_P$2") (pintype "bidirectional"))
      (node (ref "IC10") (pin "P$3") (pinfunction "GND_P$3") (pintype "bidirectional"))
      (node (ref "IC10") (pin "P$4") (pinfunction "GND_P$4") (pintype "bidirectional"))
      (node (ref "IC10") (pin "P$5") (pinfunction "GND_P$5") (pintype "bidirectional"))
      (node (ref "IC10") (pin "P$6") (pinfunction "GND_P$6") (pintype "bidirectional"))
      (node (ref "IC4") (pin "1") (pinfunction "GND_1") (pintype "input"))
      (node (ref "IC6") (pin "11") (pinfunction "GND_11") (pintype "bidirectional"))
      (node (ref "IC6") (pin "8") (pinfunction "GND_8") (pintype "bidirectional"))
      (node (ref "IC6") (pin "P$1") (pinfunction "GND_P$1") (pintype "bidirectional"))
      (node (ref "IC6") (pin "P$2") (pinfunction "GND_P$2") (pintype "bidirectional"))
      (node (ref "IC6") (pin "P$3") (pinfunction "GND_P$3") (pintype "bidirectional"))
      (node (ref "IC6") (pin "P$4") (pinfunction "GND_P$4") (pintype "bidirectional"))
      (node (ref "IC6") (pin "P$5") (pinfunction "GND_P$5") (pintype "bidirectional"))
      (node (ref "IC6") (pin "P$6") (pinfunction "GND_P$6") (pintype "bidirectional"))
      (node (ref "IC8") (pin "11") (pinfunction "GND_11") (pintype "bidirectional"))
      (node (ref "IC8") (pin "8") (pinfunction "GND_8") (pintype "bidirectional"))
      (node (ref "IC8") (pin "P$1") (pinfunction "GND_P$1") (pintype "bidirectional"))
      (node (ref "IC8") (pin "P$2") (pinfunction "GND_P$2") (pintype "bidirectional"))
      (node (ref "IC8") (pin "P$3") (pinfunction "GND_P$3") (pintype "bidirectional"))
      (node (ref "IC8") (pin "P$4") (pinfunction "GND_P$4") (pintype "bidirectional"))
      (node (ref "IC8") (pin "P$5") (pinfunction "GND_P$5") (pintype "bidirectional"))
      (node (ref "IC8") (pin "P$6") (pinfunction "GND_P$6") (pintype "bidirectional"))
      (node (ref "J10") (pin "5") (pinfunction "5_5") (pintype "bidirectional"))
      (node (ref "J12") (pin "5") (pinfunction "5_5") (pintype "bidirectional"))
      (node (ref "J8") (pin "5") (pinfunction "5_5") (pintype "bidirectional"))
      (node (ref "J9") (pin "1") (pinfunction "1_1") (pintype "bidirectional"))
      (node (ref "LDO1") (pin "2") (pinfunction "GND_2") (pintype "bidirectional"))
      (node (ref "LDO1") (pin "DGND") (pinfunction "GND_DGND") (pintype "bidirectional"))
      (node (ref "LDO1") (pin "DGND2") (pinfunction "GND_DGND2") (pintype "bidirectional"))
      (node (ref "LDO1") (pin "DGND3") (pinfunction "GND_DGND3") (pintype "bidirectional"))
      (node (ref "R6B2") (pin "2") (pinfunction "2_2") (pintype "passive"))
      (node (ref "R6B4") (pin "2") (pinfunction "2_2") (pintype "passive"))
      (node (ref "R6B6") (pin "2") (pinfunction "2_2") (pintype "passive"))
      (node (ref "R7B2") (pin "2") (pinfunction "2_2") (pintype "passive"))
      (node (ref "R7B4") (pin "2") (pinfunction "2_2") (pintype "passive"))
      (node (ref "R7B6") (pin "2") (pinfunction "2_2") (pintype "passive"))
      (node (ref "SH1") (pin "1") (pinfunction "P$1_1") (pintype "bidirectional"))
    )
    (net (code "28") (name "DGND{slash}2") (class "Default")
      (node (ref "C18A") (pin "2") (pinfunction "2_2") (pintype "passive"))
      (node (ref "C18B") (pin "2") (pinfunction "2_2") (pintype "passive"))
      (node (ref "C18D") (pin "2") (pinfunction "2_2") (pintype "passive"))
      (node (ref "C19A") (pin "2") (pinfunction "2_2") (pintype "passive"))
      (node (ref "C19A") (pin "DGND") (pinfunction "2_DGND") (pintype "passive"))
      (node (ref "C19B") (pin "2") (pinfunction "2_2") (pintype "passive"))
      (node (ref "C19B") (pin "DGND") (pinfunction "2_DGND") (pintype "passive"))
      (node (ref "C19D") (pin "2") (pinfunction "2_2") (pintype "passive"))
      (node (ref "C19D") (pin "DGND") (pinfunction "2_DGND") (pintype "passive"))
      (node (ref "C1P1") (pin "2") (pinfunction "-_2") (pintype "bidirectional"))
      (node (ref "C20A") (pin "2") (pinfunction "2_2") (pintype "passive"))
      (node (ref "C20B") (pin "2") (pinfunction "2_2") (pintype "passive"))
      (node (ref "C20D") (pin "2") (pinfunction "2_2") (pintype "passive"))
      (node (ref "C21A") (pin "2") (pinfunction "2_2") (pintype "passive"))
      (node (ref "C21B") (pin "2") (pinfunction "2_2") (pintype "passive"))
      (node (ref "C21D") (pin "2") (pinfunction "2_2") (pintype "passive"))
      (node (ref "C26A") (pin "2") (pinfunction "2_2") (pintype "passive"))
      (node (ref "C27A") (pin "2") (pinfunction "2_2") (pintype "passive"))
      (node (ref "C28A") (pin "2") (pinfunction "2_2") (pintype "passive"))
      (node (ref "C2P1") (pin "2") (pinfunction "-_2") (pintype "bidirectional"))
      (node (ref "C3P1") (pin "2") (pinfunction "-_2") (pintype "bidirectional"))
      (node (ref "C5P1") (pin "2") (pinfunction "-_2") (pintype "bidirectional"))
      (node (ref "C6P1") (pin "2") (pinfunction "-_2") (pintype "bidirectional"))
      (node (ref "C7") (pin "2") (pinfunction "-_2") (pintype "bidirectional"))
      (node (ref "C7P1") (pin "2") (pinfunction "-_2") (pintype "bidirectional"))
      (node (ref "C8") (pin "2") (pinfunction "-_2") (pintype "bidirectional"))
      (node (ref "D11") (pin "2") (pinfunction "A_2") (pintype "bidirectional"))
      (node (ref "D12") (pin "2") (pinfunction "A_2") (pintype "bidirectional"))
      (node (ref "IC1") (pin "11") (pinfunction "GND_11") (pintype "bidirectional"))
      (node (ref "IC1") (pin "8") (pinfunction "GND_8") (pintype "bidirectional"))
      (node (ref "IC1") (pin "P$1") (pinfunction "GND_P$1") (pintype "bidirectional"))
      (node (ref "IC1") (pin "P$2") (pinfunction "GND_P$2") (pintype "bidirectional"))
      (node (ref "IC1") (pin "P$3") (pinfunction "GND_P$3") (pintype "bidirectional"))
      (node (ref "IC1") (pin "P$4") (pinfunction "GND_P$4") (pintype "bidirectional"))
      (node (ref "IC1") (pin "P$5") (pinfunction "GND_P$5") (pintype "bidirectional"))
      (node (ref "IC1") (pin "P$6") (pinfunction "GND_P$6") (pintype "bidirectional"))
      (node (ref "IC2") (pin "11") (pinfunction "GND_11") (pintype "bidirectional"))
      (node (ref "IC2") (pin "8") (pinfunction "GND_8") (pintype "bidirectional"))
      (node (ref "IC2") (pin "P$1") (pinfunction "GND_P$1") (pintype "bidirectional"))
      (node (ref "IC2") (pin "P$2") (pinfunction "GND_P$2") (pintype "bidirectional"))
      (node (ref "IC2") (pin "P$3") (pinfunction "GND_P$3") (pintype "bidirectional"))
      (node (ref "IC2") (pin "P$4") (pinfunction "GND_P$4") (pintype "bidirectional"))
      (node (ref "IC2") (pin "P$5") (pinfunction "GND_P$5") (pintype "bidirectional"))
      (node (ref "IC2") (pin "P$6") (pinfunction "GND_P$6") (pintype "bidirectional"))
      (node (ref "IC3") (pin "1") (pinfunction "GND_1") (pintype "input"))
      (node (ref "IC5") (pin "11") (pinfunction "GND_11") (pintype "bidirectional"))
      (node (ref "IC5") (pin "8") (pinfunction "GND_8") (pintype "bidirectional"))
      (node (ref "IC5") (pin "P$1") (pinfunction "GND_P$1") (pintype "bidirectional"))
      (node (ref "IC5") (pin "P$2") (pinfunction "GND_P$2") (pintype "bidirectional"))
      (node (ref "IC5") (pin "P$3") (pinfunction "GND_P$3") (pintype "bidirectional"))
      (node (ref "IC5") (pin "P$4") (pinfunction "GND_P$4") (pintype "bidirectional"))
      (node (ref "IC5") (pin "P$5") (pinfunction "GND_P$5") (pintype "bidirectional"))
      (node (ref "IC5") (pin "P$6") (pinfunction "GND_P$6") (pintype "bidirectional"))
      (node (ref "J1") (pin "5") (pinfunction "5_5") (pintype "bidirectional"))
      (node (ref "J17") (pin "5") (pinfunction "5_5") (pintype "bidirectional"))
      (node (ref "J5") (pin "5") (pinfunction "5_5") (pintype "bidirectional"))
      (node (ref "J7") (pin "6") (pinfunction "6_6") (pintype "bidirectional"))
      (node (ref "LDO7") (pin "2") (pinfunction "GND_2") (pintype "bidirectional"))
      (node (ref "LDO7") (pin "DGND") (pinfunction "GND_DGND") (pintype "bidirectional"))
      (node (ref "LDO7") (pin "DGND2") (pinfunction "GND_DGND2") (pintype "bidirectional"))
      (node (ref "LDO7") (pin "DGND3") (pinfunction "GND_DGND3") (pintype "bidirectional"))
      (node (ref "R6A") (pin "2") (pinfunction "2_2") (pintype "passive"))
      (node (ref "R6B") (pin "2") (pinfunction "2_2") (pintype "passive"))
      (node (ref "R6D") (pin "2") (pinfunction "2_2") (pintype "passive"))
      (node (ref "R7A") (pin "2") (pinfunction "2_2") (pintype "passive"))
      (node (ref "R7B") (pin "2") (pinfunction "2_2") (pintype "passive"))
      (node (ref "R7D") (pin "2") (pinfunction "2_2") (pintype "passive"))
      (node (ref "SH2") (pin "1") (pinfunction "P$1_1") (pintype "bidirectional"))
    )
    (net (code "29") (name "L+") (class "Default")
      (node (ref "R23O") (pin "1") (pinfunction "1_1") (pintype "passive"))
      (node (ref "R24O") (pin "1") (pinfunction "1_1") (pintype "passive"))
      (node (ref "R4") (pin "2") (pinfunction "2_2") (pintype "passive"))
    )
    (net (code "30") (name "L-") (class "Default")
      (node (ref "R25O") (pin "1") (pinfunction "1_1") (pintype "passive"))
      (node (ref "R26O") (pin "1") (pinfunction "1_1") (pintype "passive"))
      (node (ref "R3") (pin "2") (pinfunction "2_2") (pintype "passive"))
    )
    (net (code "31") (name "L_OUT") (class "Default")
      (node (ref "C21O1") (pin "1") (pinfunction "1_1") (pintype "passive"))
      (node (ref "C21O1") (pin "4") (pinfunction "1_4") (pintype "passive"))
      (node (ref "J3") (pin "2") (pinfunction "TIP_2") (pintype "bidirectional"))
      (node (ref "R20O2") (pin "2") (pinfunction "2_2") (pintype "passive"))
      (node (ref "Z5") (pin "1") (pinfunction "C_1") (pintype "passive"))
    )
    (net (code "32") (name "Net-(C1P-+)") (class "Default")
      (node (ref "C1P") (pin "1") (pinfunction "+_1") (pintype "bidirectional"))
      (node (ref "D10") (pin "1") (pinfunction "K_1") (pintype "bidirectional"))
      (node (ref "D9") (pin "1") (pinfunction "K_1") (pintype "bidirectional"))
      (node (ref "J6") (pin "4") (pinfunction "4_4") (pintype "bidirectional"))
    )
    (net (code "33") (name "Net-(C1P1-+)") (class "Default")
      (node (ref "C1P1") (pin "1") (pinfunction "+_1") (pintype "bidirectional"))
      (node (ref "D13") (pin "1") (pinfunction "K_1") (pintype "bidirectional"))
      (node (ref "D14") (pin "1") (pinfunction "K_1") (pintype "bidirectional"))
      (node (ref "J6") (pin "10") (pinfunction "10_10") (pintype "bidirectional"))
    )
    (net (code "34") (name "Net-(C1P2-+)") (class "Default")
      (node (ref "C1P2") (pin "1") (pinfunction "+_1") (pintype "bidirectional"))
      (node (ref "D17") (pin "1") (pinfunction "K_1") (pintype "bidirectional"))
      (node (ref "D18") (pin "1") (pinfunction "K_1") (pintype "bidirectional"))
      (node (ref "J4") (pin "8") (pinfunction "8_8") (pintype "bidirectional"))
    )
    (net (code "35") (name "Net-(C1P3-+)") (class "Default")
      (node (ref "C1P3") (pin "1") (pinfunction "+_1") (pintype "bidirectional"))
      (node (ref "D21") (pin "1") (pinfunction "K_1") (pintype "bidirectional"))
      (node (ref "D22") (pin "1") (pinfunction "K_1") (pintype "bidirectional"))
      (node (ref "J4") (pin "2") (pinfunction "2_2") (pintype "bidirectional"))
    )
    (net (code "36") (name "Net-(C2O-Pad1)") (class "Default")
      (node (ref "C2O") (pin "1") (pinfunction "1_1") (pintype "passive"))
      (node (ref "R17") (pin "2") (pinfunction "2_2") (pintype "passive"))
      (node (ref "SX1") (pin "6") (pinfunction "6_6") (pintype "passive"))
    )
    (net (code "37") (name "Net-(C2O-Pad2)") (class "Default")
      (node (ref "C2O") (pin "2") (pinfunction "2_2") (pintype "passive"))
      (node (ref "R3O") (pin "1") (pinfunction "1_1") (pintype "passive"))
      (node (ref "R8") (pin "2") (pinfunction "2_2") (pintype "passive"))
    )
    (net (code "38") (name "Net-(C2O1-Pad1)") (class "Default")
      (node (ref "C2O1") (pin "1") (pinfunction "1_1") (pintype "passive"))
      (node (ref "R18") (pin "1") (pinfunction "1_1") (pintype "passive"))
      (node (ref "SX2") (pin "6") (pinfunction "6_6") (pintype "passive"))
    )
    (net (code "39") (name "Net-(C2O1-Pad2)") (class "Default")
      (node (ref "C2O1") (pin "2") (pinfunction "2_2") (pintype "passive"))
      (node (ref "R14") (pin "2") (pinfunction "2_2") (pintype "passive"))
      (node (ref "R3O1") (pin "1") (pinfunction "1_1") (pintype "passive"))
    )
    (net (code "40") (name "Net-(C2P-+)") (class "Default")
      (node (ref "C2P") (pin "1") (pinfunction "+_1") (pintype "bidirectional"))
      (node (ref "J6") (pin "5") (pinfunction "5_5") (pintype "bidirectional"))
      (node (ref "R6P") (pin "2") (pinfunction "2_2") (pintype "passive"))
    )
    (net (code "41") (name "Net-(C2P1-+)") (class "Default")
      (node (ref "C2P1") (pin "1") (pinfunction "+_1") (pintype "bidirectional"))
      (node (ref "J6") (pin "11") (pinfunction "11_11") (pintype "bidirectional"))
      (node (ref "R6P1") (pin "2") (pinfunction "2_2") (pintype "passive"))
    )
    (net (code "42") (name "Net-(C2P2-+)") (class "Default")
      (node (ref "C2P2") (pin "1") (pinfunction "+_1") (pintype "bidirectional"))
      (node (ref "J4") (pin "7") (pinfunction "7_7") (pintype "bidirectional"))
      (node (ref "R6P2") (pin "2") (pinfunction "2_2") (pintype "passive"))
    )
    (net (code "43") (name "Net-(C2P3-+)") (class "Default")
      (node (ref "C2P3") (pin "1") (pinfunction "+_1") (pintype "bidirectional"))
      (node (ref "J4") (pin "1") (pinfunction "1_1") (pintype "bidirectional"))
      (node (ref "R6P3") (pin "2") (pinfunction "2_2") (pintype "passive"))
    )
    (net (code "44") (name "Net-(C4P-+)") (class "Default")
      (node (ref "C4P") (pin "1") (pinfunction "+_1") (pintype "bidirectional"))
      (node (ref "R2P") (pin "1") (pinfunction "1_1") (pintype "passive"))
      (node (ref "R3P") (pin "2") (pinfunction "2_2") (pintype "passive"))
      (node (ref "R4P") (pin "1") (pinfunction "1_1") (pintype "passive"))
      (node (ref "R5P") (pin "2") (pinfunction "2_2") (pintype "passive"))
    )
    (net (code "45") (name "Net-(C4P1-+)") (class "Default")
      (node (ref "C4P1") (pin "1") (pinfunction "+_1") (pintype "bidirectional"))
      (node (ref "R2P1") (pin "1") (pinfunction "1_1") (pintype "passive"))
      (node (ref "R3P1") (pin "2") (pinfunction "2_2") (pintype "passive"))
      (node (ref "R4P1") (pin "1") (pinfunction "1_1") (pintype "passive"))
      (node (ref "R5P1") (pin "2") (pinfunction "2_2") (pintype "passive"))
    )
    (net (code "46") (name "Net-(C11O-+)") (class "Default")
      (node (ref "C11O") (pin "1") (pinfunction "+_1") (pintype "passive"))
      (node (ref "J13") (pin "6") (pinfunction "6_6") (pintype "passive"))
    )
    (net (code "47") (name "Net-(C11O--)") (class "Default")
      (node (ref "C11O") (pin "2") (pinfunction "-_2") (pintype "passive"))
      (node (ref "R12O") (pin "2") (pinfunction "2_2") (pintype "passive"))
      (node (ref "R19O") (pin "2") (pinfunction "2_2") (pintype "passive"))
    )
    (net (code "48") (name "Net-(C12O-+)") (class "Default")
      (node (ref "C12O") (pin "1") (pinfunction "+_1") (pintype "passive"))
      (node (ref "J13") (pin "1") (pinfunction "1_1") (pintype "passive"))
    )
    (net (code "49") (name "Net-(C12O--)") (class "Default")
      (node (ref "C12O") (pin "2") (pinfunction "-_2") (pintype "passive"))
      (node (ref "R18O") (pin "2") (pinfunction "2_2") (pintype "passive"))
      (node (ref "R20O") (pin "1") (pinfunction "1_1") (pintype "passive"))
    )
    (net (code "50") (name "Net-(C13O-+)") (class "Default")
      (node (ref "C13O") (pin "1") (pinfunction "+_1") (pintype "passive"))
      (node (ref "J13") (pin "4") (pinfunction "4_4") (pintype "passive"))
    )
    (net (code "51") (name "Net-(C13O--)") (class "Default")
      (node (ref "C13O") (pin "2") (pinfunction "-_2") (pintype "passive"))
      (node (ref "R14O") (pin "2") (pinfunction "2_2") (pintype "passive"))
      (node (ref "R21O") (pin "2") (pinfunction "2_2") (pintype "passive"))
    )
    (net (code "52") (name "Net-(C14O-+)") (class "Default")
      (node (ref "C14O") (pin "1") (pinfunction "+_1") (pintype "passive"))
      (node (ref "J13") (pin "3") (pinfunction "3_3") (pintype "passive"))
    )
    (net (code "53") (name "Net-(C14O--)") (class "Default")
      (node (ref "C14O") (pin "2") (pinfunction "-_2") (pintype "passive"))
      (node (ref "R11O") (pin "1") (pinfunction "1_1") (pintype "passive"))
      (node (ref "R16O") (pin "2") (pinfunction "2_2") (pintype "passive"))
    )
    (net (code "54") (name "Net-(C15O-+)") (class "Default")
      (node (ref "C15O") (pin "1") (pinfunction "+_1") (pintype "passive"))
      (node (ref "J2") (pin "6") (pinfunction "6_6") (pintype "passive"))
    )
    (net (code "55") (name "Net-(C15O--)") (class "Default")
      (node (ref "C15O") (pin "2") (pinfunction "-_2") (pintype "passive"))
      (node (ref "R24O") (pin "2") (pinfunction "2_2") (pintype "passive"))
      (node (ref "R28O") (pin "2") (pinfunction "2_2") (pintype "passive"))
    )
    (net (code "56") (name "Net-(C24O-+)") (class "Default")
      (node (ref "C24O") (pin "1") (pinfunction "+_1") (pintype "passive"))
      (node (ref "J2") (pin "1") (pinfunction "1_1") (pintype "passive"))
    )
    (net (code "57") (name "Net-(C24O--)") (class "Default")
      (node (ref "C24O") (pin "2") (pinfunction "-_2") (pintype "passive"))
      (node (ref "R23O") (pin "2") (pinfunction "2_2") (pintype "passive"))
      (node (ref "R29O") (pin "1") (pinfunction "1_1") (pintype "passive"))
    )
    (net (code "58") (name "Net-(C25O-+)") (class "Default")
      (node (ref "C25O") (pin "1") (pinfunction "+_1") (pintype "passive"))
      (node (ref "J2") (pin "4") (pinfunction "4_4") (pintype "passive"))
    )
    (net (code "59") (name "Net-(C25O--)") (class "Default")
      (node (ref "C25O") (pin "2") (pinfunction "-_2") (pintype "passive"))
      (node (ref "R25O") (pin "2") (pinfunction "2_2") (pintype "passive"))
      (node (ref "R30O") (pin "2") (pinfunction "2_2") (pintype "passive"))
    )
    (net (code "60") (name "Net-(C26O-+)") (class "Default")
      (node (ref "C26O") (pin "1") (pinfunction "+_1") (pintype "passive"))
      (node (ref "J2") (pin "3") (pinfunction "3_3") (pintype "passive"))
    )
    (net (code "61") (name "Net-(C26O--)") (class "Default")
      (node (ref "C26O") (pin "2") (pinfunction "-_2") (pintype "passive"))
      (node (ref "R22O") (pin "1") (pinfunction "1_1") (pintype "passive"))
      (node (ref "R26O") (pin "2") (pinfunction "2_2") (pintype "passive"))
    )
    (net (code "62") (name "Net-(D1-A)") (class "Default")
      (node (ref "D1") (pin "2") (pinfunction "A_2") (pintype "passive"))
      (node (ref "R1") (pin "1") (pinfunction "1_1") (pintype "passive"))
      (node (ref "SX3") (pin "2") (pinfunction "2_2") (pintype "passive"))
    )
    (net (code "63") (name "Net-(D1-C)") (class "Default")
      (node (ref "D1") (pin "1") (pinfunction "C_1") (pintype "passive"))
      (node (ref "D2") (pin "1") (pinfunction "C_1") (pintype "passive"))
      (node (ref "SX3") (pin "3") (pinfunction "3_3") (pintype "passive"))
      (node (ref "SX3") (pin "8") (pinfunction "8_8") (pintype "passive"))
      (node (ref "U1") (pin "3") (pinfunction "IN_3") (pintype "input"))
    )
    (net (code "64") (name "Net-(D2-A)") (class "Default")
      (node (ref "D2") (pin "2") (pinfunction "A_2") (pintype "passive"))
      (node (ref "R2") (pin "1") (pinfunction "1_1") (pintype "passive"))
      (node (ref "SX3") (pin "7") (pinfunction "7_7") (pintype "passive"))
    )
    (net (code "65") (name "Net-(D3-A)") (class "Default")
      (node (ref "D3") (pin "2") (pinfunction "A_2") (pintype "passive"))
      (node (ref "R7") (pin "1") (pinfunction "1_1") (pintype "passive"))
      (node (ref "SX1") (pin "7") (pinfunction "7_7") (pintype "passive"))
    )
    (net (code "66") (name "Net-(D3-C)") (class "Default")
      (node (ref "C21O") (pin "2") (pinfunction "2_2") (pintype "passive"))
      (node (ref "C21O") (pin "3") (pinfunction "2_3") (pintype "passive"))
      (node (ref "D3") (pin "1") (pinfunction "C_1") (pintype "passive"))
      (node (ref "SX1") (pin "1") (pinfunction "1_1") (pintype "passive"))
      (node (ref "SX1") (pin "8") (pinfunction "8_8") (pintype "passive"))
    )
    (net (code "67") (name "Net-(D4-A)") (class "Default")
      (node (ref "D4") (pin "2") (pinfunction "A_2") (pintype "passive"))
      (node (ref "R3") (pin "1") (pinfunction "1_1") (pintype "passive"))
      (node (ref "SX4") (pin "2") (pinfunction "2_2") (pintype "passive"))
    )
    (net (code "68") (name "Net-(D4-C)") (class "Default")
      (node (ref "D4") (pin "1") (pinfunction "C_1") (pintype "passive"))
      (node (ref "D5") (pin "1") (pinfunction "C_1") (pintype "passive"))
      (node (ref "SX4") (pin "3") (pinfunction "3_3") (pintype "passive"))
      (node (ref "SX4") (pin "8") (pinfunction "8_8") (pintype "passive"))
      (node (ref "U2") (pin "3") (pinfunction "IN_3") (pintype "input"))
    )
    (net (code "69") (name "Net-(D5-A)") (class "Default")
      (node (ref "D5") (pin "2") (pinfunction "A_2") (pintype "passive"))
      (node (ref "R4") (pin "1") (pinfunction "1_1") (pintype "passive"))
      (node (ref "SX4") (pin "7") (pinfunction "7_7") (pintype "passive"))
    )
    (net (code "70") (name "Net-(D6-A)") (class "Default")
      (node (ref "D6") (pin "2") (pinfunction "A_2") (pintype "passive"))
      (node (ref "R13") (pin "1") (pinfunction "1_1") (pintype "passive"))
      (node (ref "SX2") (pin "7") (pinfunction "7_7") (pintype "passive"))
    )
    (net (code "71") (name "Net-(D6-C)") (class "Default")
      (node (ref "C21O1") (pin "2") (pinfunction "2_2") (pintype "passive"))
      (node (ref "C21O1") (pin "3") (pinfunction "2_3") (pintype "passive"))
      (node (ref "D6") (pin "1") (pinfunction "C_1") (pintype "passive"))
      (node (ref "SX2") (pin "1") (pinfunction "1_1") (pintype "passive"))
      (node (ref "SX2") (pin "8") (pinfunction "8_8") (pintype "passive"))
    )
    (net (code "72") (name "Net-(IC1-ILIM)") (class "Default")
      (node (ref "IC1") (pin "5") (pinfunction "ILIM_5") (pintype "bidirectional"))
      (node (ref "J1") (pin "2") (pinfunction "2_2") (pintype "bidirectional"))
      (node (ref "R6D") (pin "1") (pinfunction "1_1") (pintype "passive"))
    )
    (net (code "73") (name "Net-(IC1-PG)") (class "Default")
      (node (ref "IC1") (pin "4") (pinfunction "PG_4") (pintype "bidirectional"))
      (node (ref "J1") (pin "1") (pinfunction "1_1") (pintype "bidirectional"))
      (node (ref "R8D") (pin "2") (pinfunction "2_2") (pintype "passive"))
    )
    (net (code "74") (name "Net-(IC1-PGFB)") (class "Default")
      (node (ref "IC1") (pin "6") (pinfunction "PGFB_6") (pintype "bidirectional"))
      (node (ref "J1") (pin "3") (pinfunction "3_3") (pintype "bidirectional"))
    )
    (net (code "75") (name "Net-(IC1-SET)") (class "Default")
      (node (ref "C19D") (pin "1") (pinfunction "1_1") (pintype "passive"))
      (node (ref "IC1") (pin "7") (pinfunction "SET_7") (pintype "bidirectional"))
      (node (ref "J1") (pin "4") (pinfunction "4_4") (pintype "bidirectional"))
      (node (ref "R7D") (pin "1") (pinfunction "1_1") (pintype "passive"))
    )
    (net (code "76") (name "Net-(IC2-ILIM)") (class "Default")
      (node (ref "IC2") (pin "5") (pinfunction "ILIM_5") (pintype "bidirectional"))
      (node (ref "J5") (pin "2") (pinfunction "2_2") (pintype "bidirectional"))
      (node (ref "R6A") (pin "1") (pinfunction "1_1") (pintype "passive"))
    )
    (net (code "77") (name "Net-(IC2-PG)") (class "Default")
      (node (ref "IC2") (pin "4") (pinfunction "PG_4") (pintype "bidirectional"))
      (node (ref "J5") (pin "1") (pinfunction "1_1") (pintype "bidirectional"))
      (node (ref "R8A") (pin "2") (pinfunction "2_2") (pintype "passive"))
    )
    (net (code "78") (name "Net-(IC2-PGFB)") (class "Default")
      (node (ref "IC2") (pin "6") (pinfunction "PGFB_6") (pintype "bidirectional"))
      (node (ref "J5") (pin "3") (pinfunction "3_3") (pintype "bidirectional"))
    )
    (net (code "79") (name "Net-(IC2-SET)") (class "Default")
      (node (ref "C19A") (pin "1") (pinfunction "1_1") (pintype "passive"))
      (node (ref "IC2") (pin "7") (pinfunction "SET_7") (pintype "bidirectional"))
      (node (ref "J5") (pin "4") (pinfunction "4_4") (pintype "bidirectional"))
      (node (ref "R7A") (pin "1") (pinfunction "1_1") (pintype "passive"))
    )
    (net (code "80") (name "Net-(IC5-ILIM)") (class "Default")
      (node (ref "IC5") (pin "5") (pinfunction "ILIM_5") (pintype "bidirectional"))
      (node (ref "J17") (pin "2") (pinfunction "2_2") (pintype "bidirectional"))
      (node (ref "R6B") (pin "1") (pinfunction "1_1") (pintype "passive"))
    )
    (net (code "81") (name "Net-(IC5-PG)") (class "Default")
      (node (ref "IC5") (pin "4") (pinfunction "PG_4") (pintype "bidirectional"))
      (node (ref "J17") (pin "1") (pinfunction "1_1") (pintype "bidirectional"))
      (node (ref "R8B") (pin "2") (pinfunction "2_2") (pintype "passive"))
    )
    (net (code "82") (name "Net-(IC5-PGFB)") (class "Default")
      (node (ref "IC5") (pin "6") (pinfunction "PGFB_6") (pintype "bidirectional"))
      (node (ref "J17") (pin "3") (pinfunction "3_3") (pintype "bidirectional"))
    )
    (net (code "83") (name "Net-(IC5-SET)") (class "Default")
      (node (ref "C19B") (pin "1") (pinfunction "1_1") (pintype "passive"))
      (node (ref "IC5") (pin "7") (pinfunction "SET_7") (pintype "bidirectional"))
      (node (ref "J17") (pin "4") (pinfunction "4_4") (pintype "bidirectional"))
      (node (ref "R7B") (pin "1") (pinfunction "1_1") (pintype "passive"))
    )
    (net (code "84") (name "Net-(IC6-ILIM)") (class "Default")
      (node (ref "IC6") (pin "5") (pinfunction "ILIM_5") (pintype "bidirectional"))
      (node (ref "J8") (pin "2") (pinfunction "2_2") (pintype "bidirectional"))
      (node (ref "R6B2") (pin "1") (pinfunction "1_1") (pintype "passive"))
    )
    (net (code "85") (name "Net-(IC6-PG)") (class "Default")
      (node (ref "IC6") (pin "4") (pinfunction "PG_4") (pintype "bidirectional"))
      (node (ref "J8") (pin "1") (pinfunction "1_1") (pintype "bidirectional"))
      (node (ref "R8B2") (pin "2") (pinfunction "2_2") (pintype "passive"))
    )
    (net (code "86") (name "Net-(IC6-PGFB)") (class "Default")
      (node (ref "IC6") (pin "6") (pinfunction "PGFB_6") (pintype "bidirectional"))
      (node (ref "J8") (pin "3") (pinfunction "3_3") (pintype "bidirectional"))
    )
    (net (code "87") (name "Net-(IC6-SET)") (class "Default")
      (node (ref "C19B2") (pin "1") (pinfunction "1_1") (pintype "passive"))
      (node (ref "IC6") (pin "7") (pinfunction "SET_7") (pintype "bidirectional"))
      (node (ref "J8") (pin "4") (pinfunction "4_4") (pintype "bidirectional"))
      (node (ref "R7B2") (pin "1") (pinfunction "1_1") (pintype "passive"))
    )
    (net (code "88") (name "Net-(IC8-ILIM)") (class "Default")
      (node (ref "IC8") (pin "5") (pinfunction "ILIM_5") (pintype "bidirectional"))
      (node (ref "J10") (pin "2") (pinfunction "2_2") (pintype "bidirectional"))
      (node (ref "R6B4") (pin "1") (pinfunction "1_1") (pintype "passive"))
    )
    (net (code "89") (name "Net-(IC8-PG)") (class "Default")
      (node (ref "IC8") (pin "4") (pinfunction "PG_4") (pintype "bidirectional"))
      (node (ref "J10") (pin "1") (pinfunction "1_1") (pintype "bidirectional"))
      (node (ref "R8B4") (pin "2") (pinfunction "2_2") (pintype "passive"))
    )
    (net (code "90") (name "Net-(IC8-PGFB)") (class "Default")
      (node (ref "IC8") (pin "6") (pinfunction "PGFB_6") (pintype "bidirectional"))
      (node (ref "J10") (pin "3") (pinfunction "3_3") (pintype "bidirectional"))
    )
    (net (code "91") (name "Net-(IC8-SET)") (class "Default")
      (node (ref "C19B4") (pin "1") (pinfunction "1_1") (pintype "passive"))
      (node (ref "IC8") (pin "7") (pinfunction "SET_7") (pintype "bidirectional"))
      (node (ref "J10") (pin "4") (pinfunction "4_4") (pintype "bidirectional"))
      (node (ref "R7B4") (pin "1") (pinfunction "1_1") (pintype "passive"))
    )
    (net (code "92") (name "Net-(IC10-ILIM)") (class "Default")
      (node (ref "IC10") (pin "5") (pinfunction "ILIM_5") (pintype "bidirectional"))
      (node (ref "J12") (pin "2") (pinfunction "2_2") (pintype "bidirectional"))
      (node (ref "R6B6") (pin "1") (pinfunction "1_1") (pintype "passive"))
    )
    (net (code "93") (name "Net-(IC10-PG)") (class "Default")
      (node (ref "IC10") (pin "4") (pinfunction "PG_4") (pintype "bidirectional"))
      (node (ref "J12") (pin "1") (pinfunction "1_1") (pintype "bidirectional"))
      (node (ref "R8B6") (pin "2") (pinfunction "2_2") (pintype "passive"))
    )
    (net (code "94") (name "Net-(IC10-PGFB)") (class "Default")
      (node (ref "IC10") (pin "6") (pinfunction "PGFB_6") (pintype "bidirectional"))
      (node (ref "J12") (pin "3") (pinfunction "3_3") (pintype "bidirectional"))
    )
    (net (code "95") (name "Net-(IC10-SET)") (class "Default")
      (node (ref "C19B6") (pin "1") (pinfunction "1_1") (pintype "passive"))
      (node (ref "IC10") (pin "7") (pinfunction "SET_7") (pintype "bidirectional"))
      (node (ref "J12") (pin "4") (pinfunction "4_4") (pintype "bidirectional"))
      (node (ref "R7B6") (pin "1") (pinfunction "1_1") (pintype "passive"))
    )
    (net (code "96") (name "Net-(R5-Pad1)") (class "Default")
      (node (ref "R5") (pin "1") (pinfunction "1_1") (pintype "passive"))
      (node (ref "SX3") (pin "1") (pinfunction "1_1") (pintype "passive"))
    )
    (net (code "97") (name "Net-(R11-Pad1)") (class "Default")
      (node (ref "R11") (pin "1") (pinfunction "1_1") (pintype "passive"))
      (node (ref "SX4") (pin "1") (pinfunction "1_1") (pintype "passive"))
    )
    (net (code "98") (name "Net-(R13-Pad2)") (class "Default")
      (node (ref "R13") (pin "2") (pinfunction "2_2") (pintype "passive"))
      (node (ref "R20") (pin "2") (pinfunction "2_2") (pintype "passive"))
      (node (ref "SX4") (pin "6") (pinfunction "6_6") (pintype "passive"))
    )
    (net (code "99") (name "Net-(R19-Pad1)") (class "Default")
      (node (ref "R19") (pin "1") (pinfunction "1_1") (pintype "passive"))
      (node (ref "R7") (pin "2") (pinfunction "2_2") (pintype "passive"))
      (node (ref "SX3") (pin "6") (pinfunction "6_6") (pintype "passive"))
    )
    (net (code "100") (name "Net-(U1-OUT)") (class "Default")
      (node (ref "R10") (pin "2") (pinfunction "2_2") (pintype "passive"))
      (node (ref "U1") (pin "2") (pinfunction "OUT_2") (pintype "passive"))
    )
    (net (code "101") (name "Net-(U2-OUT)") (class "Default")
      (node (ref "R16") (pin "2") (pinfunction "2_2") (pintype "passive"))
      (node (ref "U2") (pin "2") (pinfunction "OUT_2") (pintype "passive"))
    )
    (net (code "102") (name "Net-(Z1-A)") (class "Default")
      (node (ref "Z1") (pin "2") (pinfunction "A_2") (pintype "passive"))
      (node (ref "Z2") (pin "2") (pinfunction "A_2") (pintype "passive"))
    )
    (net (code "103") (name "Net-(Z3-A)") (class "Default")
      (node (ref "R8") (pin "1") (pinfunction "1_1") (pintype "passive"))
      (node (ref "SX1") (pin "2") (pinfunction "2_2") (pintype "passive"))
      (node (ref "Z3") (pin "2") (pinfunction "A_2") (pintype "passive"))
    )
    (net (code "104") (name "Net-(Z3-C)") (class "Default")
      (node (ref "R9") (pin "2") (pinfunction "2_2") (pintype "passive"))
      (node (ref "SX1") (pin "3") (pinfunction "3_3") (pintype "passive"))
      (node (ref "Z3") (pin "1") (pinfunction "C_1") (pintype "passive"))
    )
    (net (code "105") (name "Net-(Z4-A)") (class "Default")
      (node (ref "R14") (pin "1") (pinfunction "1_1") (pintype "passive"))
      (node (ref "SX2") (pin "2") (pinfunction "2_2") (pintype "passive"))
      (node (ref "Z4") (pin "2") (pinfunction "A_2") (pintype "passive"))
    )
    (net (code "106") (name "Net-(Z4-C)") (class "Default")
      (node (ref "R15") (pin "2") (pinfunction "2_2") (pintype "passive"))
      (node (ref "SX2") (pin "3") (pinfunction "3_3") (pintype "passive"))
      (node (ref "Z4") (pin "1") (pinfunction "C_1") (pintype "passive"))
    )
    (net (code "107") (name "Net-(Z5-A)") (class "Default")
      (node (ref "Z5") (pin "2") (pinfunction "A_2") (pintype "passive"))
      (node (ref "Z6") (pin "2") (pinfunction "A_2") (pintype "passive"))
    )
    (net (code "108") (name "PE") (class "Default")
      (node (ref "J4") (pin "11") (pinfunction "11_11") (pintype "bidirectional"))
      (node (ref "J6") (pin "1") (pinfunction "1_1") (pintype "bidirectional"))
    )
    (net (code "109") (name "R+") (class "Default")
      (node (ref "R12O") (pin "1") (pinfunction "1_1") (pintype "passive"))
      (node (ref "R18O") (pin "1") (pinfunction "1_1") (pintype "passive"))
      (node (ref "R2") (pin "2") (pinfunction "2_2") (pintype "passive"))
    )
    (net (code "110") (name "R-") (class "Default")
      (node (ref "R1") (pin "2") (pinfunction "2_2") (pintype "passive"))
      (node (ref "R14O") (pin "1") (pinfunction "1_1") (pintype "passive"))
      (node (ref "R16O") (pin "1") (pinfunction "1_1") (pintype "passive"))
    )
    (net (code "111") (name "R_OUT") (class "Default")
      (node (ref "C21O") (pin "1") (pinfunction "1_1") (pintype "passive"))
      (node (ref "C21O") (pin "4") (pinfunction "1_4") (pintype "passive"))
      (node (ref "J3") (pin "3") (pinfunction "RING_3") (pintype "bidirectional"))
      (node (ref "R20O1") (pin "2") (pinfunction "2_2") (pintype "passive"))
      (node (ref "Z2") (pin "1") (pinfunction "C_1") (pintype "passive"))
    )
    (net (code "112") (name "VCC{slash}1") (class "Default")
      (node (ref "C20B2") (pin "1") (pinfunction "1_1") (pintype "passive"))
      (node (ref "C20B4") (pin "1") (pinfunction "1_1") (pintype "passive"))
      (node (ref "C20B6") (pin "1") (pinfunction "1_1") (pintype "passive"))
      (node (ref "C21B2") (pin "1") (pinfunction "1_1") (pintype "passive"))
      (node (ref "C21B4") (pin "1") (pinfunction "1_1") (pintype "passive"))
      (node (ref "C21B6") (pin "1") (pinfunction "1_1") (pintype "passive"))
      (node (ref "C3P3") (pin "1") (pinfunction "+_1") (pintype "bidirectional"))
      (node (ref "C5P3") (pin "1") (pinfunction "+_1") (pintype "bidirectional"))
      (node (ref "C6") (pin "1") (pinfunction "+_1") (pintype "bidirectional"))
      (node (ref "C6P3") (pin "1") (pinfunction "+_1") (pintype "bidirectional"))
      (node (ref "C7P3") (pin "1") (pinfunction "+_1") (pintype "bidirectional"))
      (node (ref "IC10") (pin "1") (pinfunction "IN_1") (pintype "bidirectional"))
      (node (ref "IC10") (pin "2") (pinfunction "IN_2") (pintype "bidirectional"))
      (node (ref "IC10") (pin "3") (pinfunction "EN/UV_3") (pintype "bidirectional"))
      (node (ref "IC4") (pin "3") (pinfunction "IN_3") (pintype "input"))
      (node (ref "IC6") (pin "1") (pinfunction "IN_1") (pintype "bidirectional"))
      (node (ref "IC6") (pin "2") (pinfunction "IN_2") (pintype "bidirectional"))
      (node (ref "IC6") (pin "3") (pinfunction "EN/UV_3") (pintype "bidirectional"))
      (node (ref "IC8") (pin "1") (pinfunction "IN_1") (pintype "bidirectional"))
      (node (ref "IC8") (pin "2") (pinfunction "IN_2") (pintype "bidirectional"))
      (node (ref "IC8") (pin "3") (pinfunction "EN/UV_3") (pintype "bidirectional"))
      (node (ref "J10") (pin "7") (pinfunction "7_7") (pintype "bidirectional"))
      (node (ref "J10") (pin "8") (pinfunction "8_8") (pintype "bidirectional"))
      (node (ref "J12") (pin "7") (pinfunction "7_7") (pintype "bidirectional"))
      (node (ref "J12") (pin "8") (pinfunction "8_8") (pintype "bidirectional"))
      (node (ref "J8") (pin "7") (pinfunction "7_7") (pintype "bidirectional"))
      (node (ref "J8") (pin "8") (pinfunction "8_8") (pintype "bidirectional"))
      (node (ref "R6P3") (pin "1") (pinfunction "1_1") (pintype "passive"))
      (node (ref "R8B2") (pin "1") (pinfunction "1_1") (pintype "passive"))
      (node (ref "R8B4") (pin "1") (pinfunction "1_1") (pintype "passive"))
      (node (ref "R8B6") (pin "1") (pinfunction "1_1") (pintype "passive"))
    )
    (net (code "113") (name "VCC{slash}2") (class "Default")
      (node (ref "C20B") (pin "1") (pinfunction "1_1") (pintype "passive"))
      (node (ref "C20D") (pin "1") (pinfunction "1_1") (pintype "passive"))
      (node (ref "C21B") (pin "1") (pinfunction "1_1") (pintype "passive"))
      (node (ref "C21D") (pin "1") (pinfunction "1_1") (pintype "passive"))
      (node (ref "C3P1") (pin "1") (pinfunction "+_1") (pintype "bidirectional"))
      (node (ref "C5P1") (pin "1") (pinfunction "+_1") (pintype "bidirectional"))
      (node (ref "C6P1") (pin "1") (pinfunction "+_1") (pintype "bidirectional"))
      (node (ref "C7") (pin "1") (pinfunction "+_1") (pintype "bidirectional"))
      (node (ref "C7P1") (pin "1") (pinfunction "+_1") (pintype "bidirectional"))
      (node (ref "IC1") (pin "1") (pinfunction "IN_1") (pintype "bidirectional"))
      (node (ref "IC1") (pin "2") (pinfunction "IN_2") (pintype "bidirectional"))
      (node (ref "IC1") (pin "3") (pinfunction "EN/UV_3") (pintype "bidirectional"))
      (node (ref "IC3") (pin "3") (pinfunction "IN_3") (pintype "input"))
      (node (ref "IC5") (pin "1") (pinfunction "IN_1") (pintype "bidirectional"))
      (node (ref "IC5") (pin "2") (pinfunction "IN_2") (pintype "bidirectional"))
      (node (ref "IC5") (pin "3") (pinfunction "EN/UV_3") (pintype "bidirectional"))
      (node (ref "J1") (pin "7") (pinfunction "7_7") (pintype "bidirectional"))
      (node (ref "J1") (pin "8") (pinfunction "8_8") (pintype "bidirectional"))
      (node (ref "J17") (pin "7") (pinfunction "7_7") (pintype "bidirectional"))
      (node (ref "J17") (pin "8") (pinfunction "8_8") (pintype "bidirectional"))
      (node (ref "R6P1") (pin "1") (pinfunction "1_1") (pintype "passive"))
      (node (ref "R8B") (pin "1") (pinfunction "1_1") (pintype "passive"))
      (node (ref "R8D") (pin "1") (pinfunction "1_1") (pintype "passive"))
    )
    (net (code "114") (name "unconnected-(LDO1-NC-Pad4)") (class "Default")
      (node (ref "LDO1") (pin "4") (pinfunction "NC_4") (pintype "no_connect"))
    )
    (net (code "115") (name "unconnected-(LDO7-NC-Pad4)") (class "Default")
      (node (ref "LDO7") (pin "4") (pinfunction "NC_4") (pintype "no_connect"))
    )
    (net (code "116") (name "unconnected-(SX1-Pad9)") (class "Default")
      (node (ref "SX1") (pin "9") (pinfunction "9_9") (pintype "passive"))
    )
    (net (code "117") (name "unconnected-(SX2-Pad9)") (class "Default")
      (node (ref "SX2") (pin "9") (pinfunction "9_9") (pintype "passive"))
    )
    (net (code "118") (name "unconnected-(SX3-Pad9)") (class "Default")
      (node (ref "SX3") (pin "9") (pinfunction "9_9") (pintype "passive"))
    )
    (net (code "119") (name "unconnected-(SX4-Pad9)") (class "Default")
      (node (ref "SX4") (pin "9") (pinfunction "9_9") (pintype "passive"))
    )
  )
)
